# BirdHouseSchem.net
KiCad netlist of a schematic drawn in EAGLE
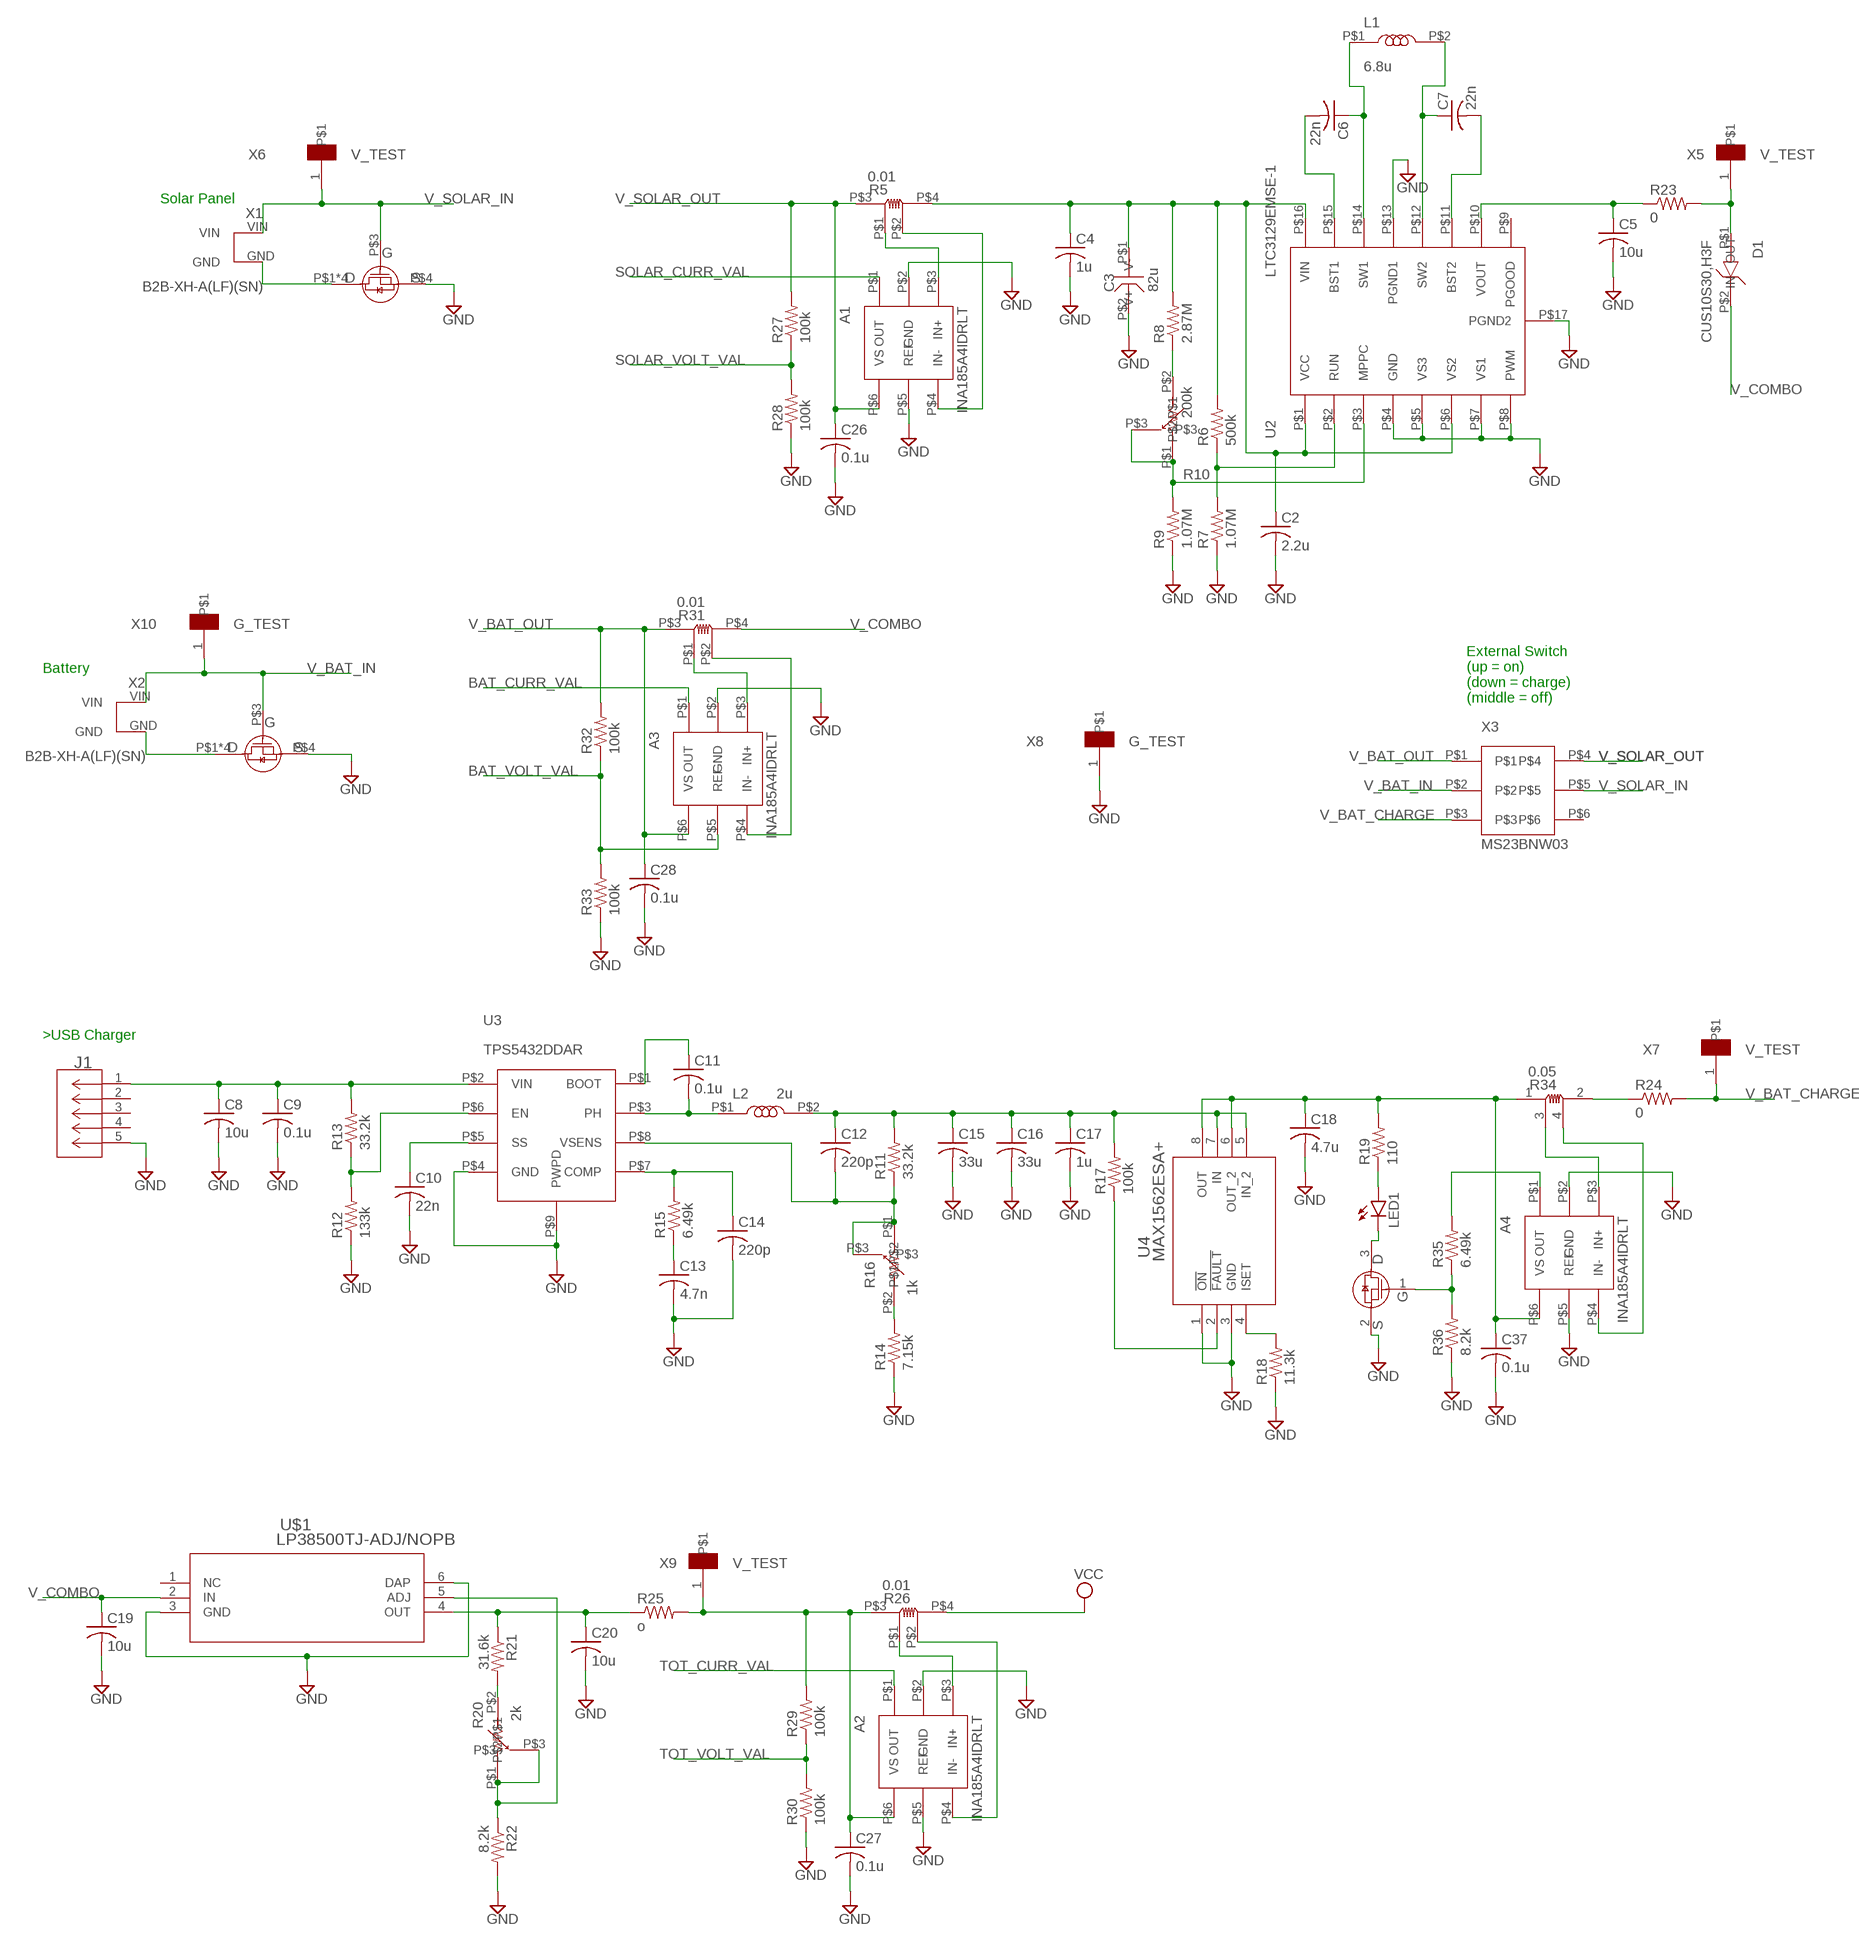
[diagram p0: schematic, sheet 1, part 1 of 2]
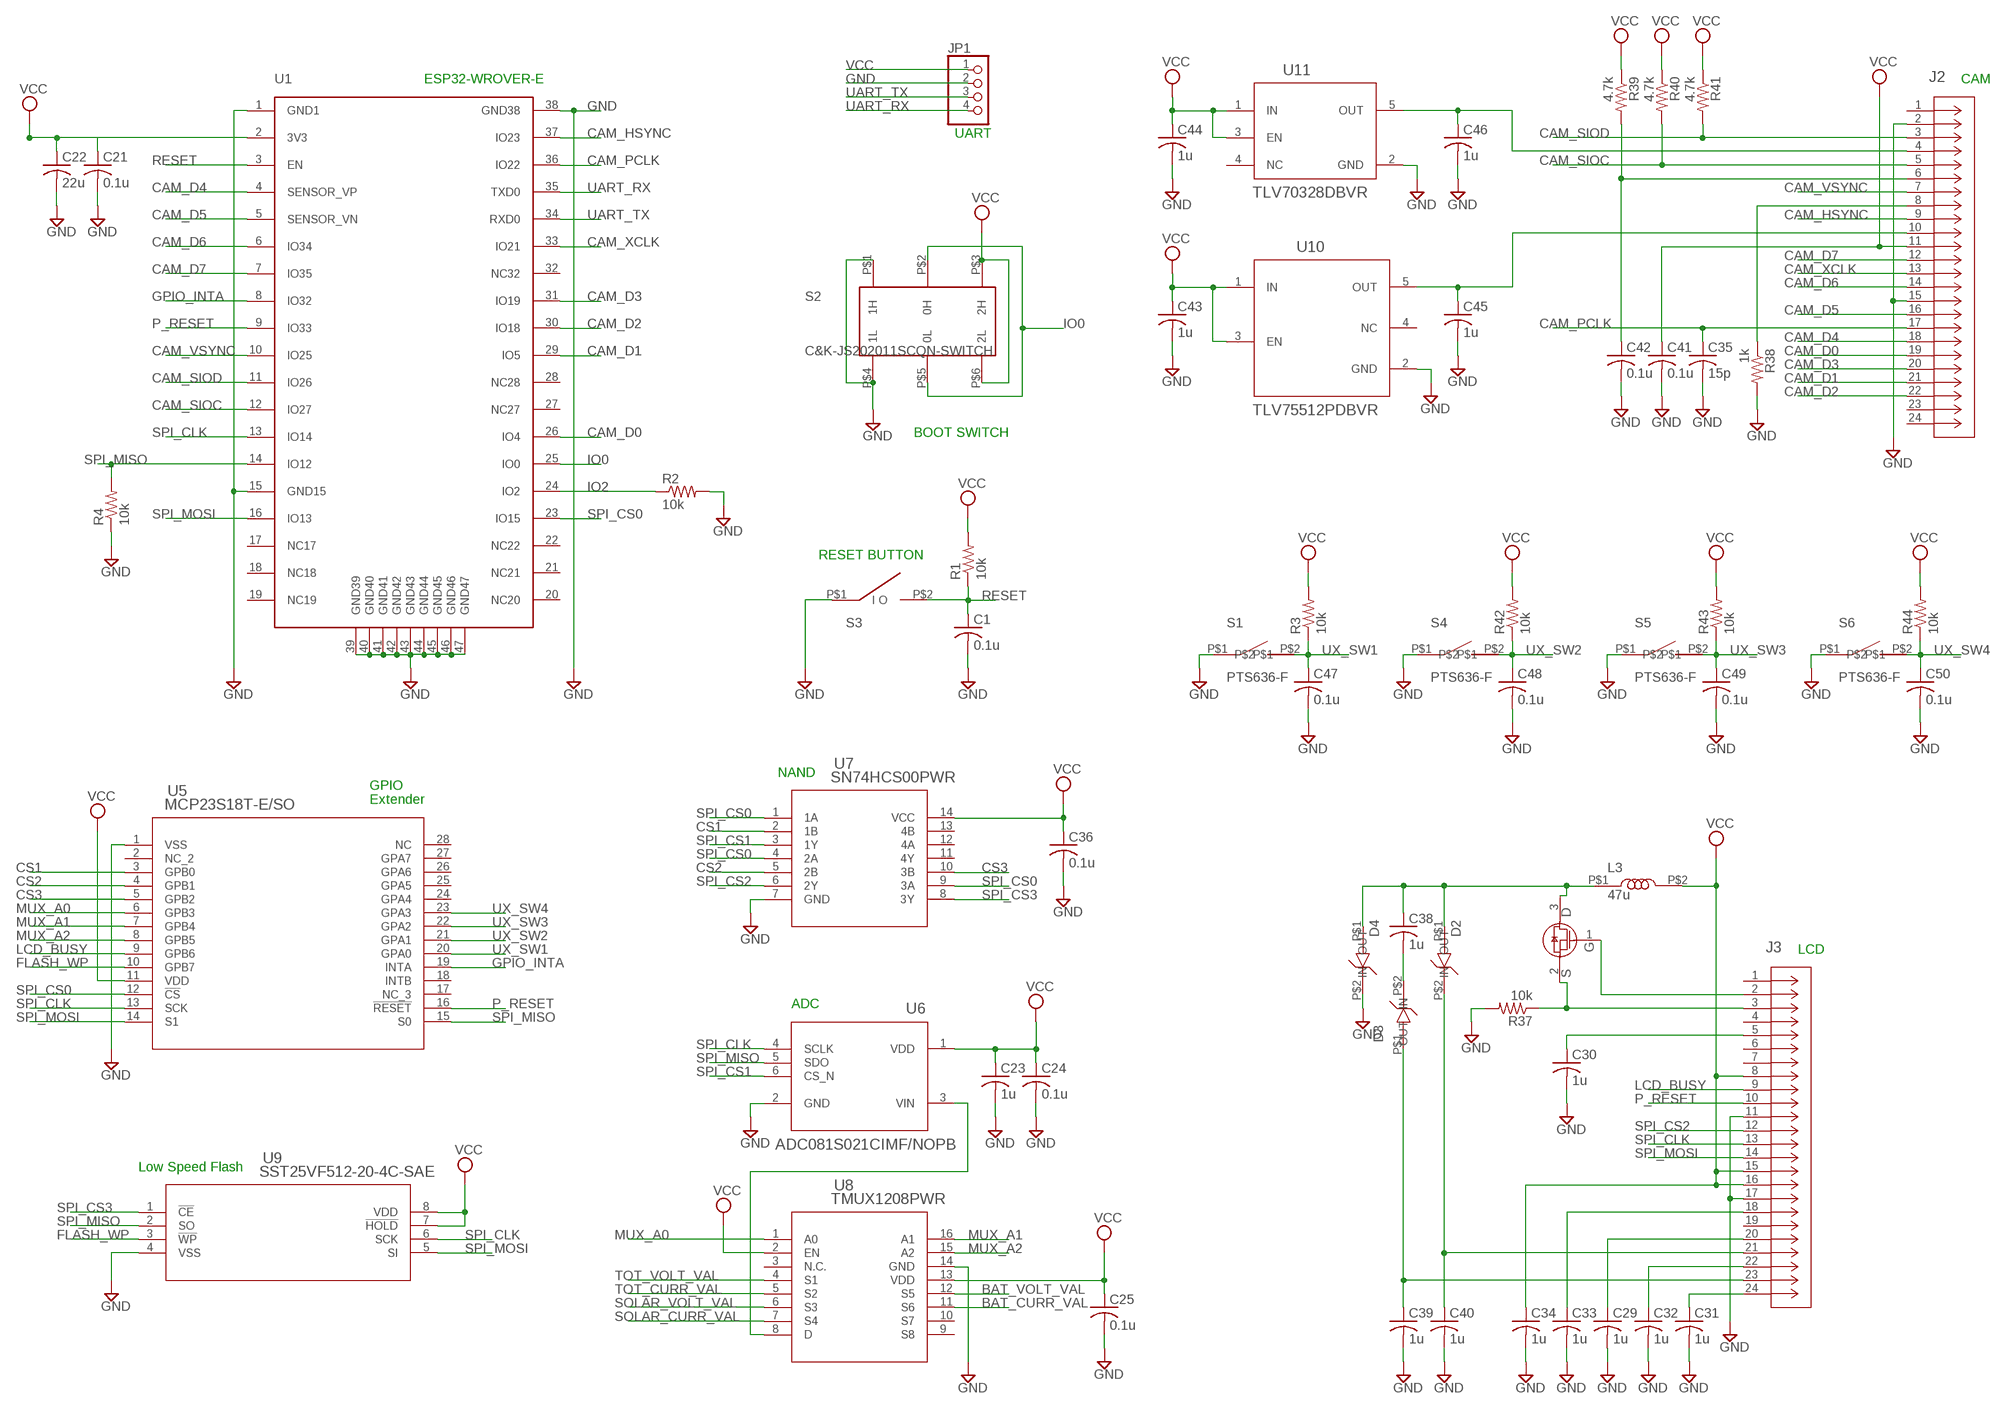
[diagram p1: schematic, sheet 1, part 2 of 2]

(export (version "E")
  (design (tool "Eeschema 10.0.6"))
  (components
    (comp (ref "A1")
      (value "INA185A4IDRLT")
      (footprint "eagle-import:SOT-6")
      (libsource (lib "eagle-import") (part "INA185A4IDRLT"))
    )
    (comp (ref "A2")
      (value "INA185A4IDRLT")
      (footprint "eagle-import:SOT-6")
      (libsource (lib "eagle-import") (part "INA185A4IDRLT"))
    )
    (comp (ref "A3")
      (value "INA185A4IDRLT")
      (footprint "eagle-import:SOT-6")
      (libsource (lib "eagle-import") (part "INA185A4IDRLT"))
    )
    (comp (ref "A4")
      (value "INA185A4IDRLT")
      (footprint "eagle-import:SOT-6")
      (libsource (lib "eagle-import") (part "INA185A4IDRLT"))
    )
    (comp (ref "C1")
      (value "0.1u")
      (footprint "eagle-import:C0805")
      (libsource (lib "eagle-import") (part "C-USC0805"))
    )
    (comp (ref "C2")
      (value "2.2u")
      (footprint "eagle-import:C0805")
      (libsource (lib "eagle-import") (part "C-USC0805"))
    )
    (comp (ref "C3")
      (value "82u")
      (footprint "eagle-import:EEE-FN1V820UP")
      (libsource (lib "eagle-import") (part "EEE-FN1V820UP"))
    )
    (comp (ref "C4")
      (value "1u")
      (footprint "eagle-import:C0805")
      (libsource (lib "eagle-import") (part "C-USC0805"))
    )
    (comp (ref "C5")
      (value "10u")
      (footprint "eagle-import:C0805")
      (libsource (lib "eagle-import") (part "C-USC0805"))
    )
    (comp (ref "C6")
      (value "22n")
      (footprint "eagle-import:C0805")
      (libsource (lib "eagle-import") (part "C-USC0805"))
    )
    (comp (ref "C7")
      (value "22n")
      (footprint "eagle-import:C0805")
      (libsource (lib "eagle-import") (part "C-USC0805"))
    )
    (comp (ref "C8")
      (value "10u")
      (footprint "eagle-import:C0805")
      (libsource (lib "eagle-import") (part "C-USC0805"))
    )
    (comp (ref "C9")
      (value "0.1u")
      (footprint "eagle-import:C0805")
      (libsource (lib "eagle-import") (part "C-USC0805"))
    )
    (comp (ref "C10")
      (value "22n")
      (footprint "eagle-import:C0805")
      (libsource (lib "eagle-import") (part "C-USC0805"))
    )
    (comp (ref "C11")
      (value "0.1u")
      (footprint "eagle-import:C0805")
      (libsource (lib "eagle-import") (part "C-USC0805"))
    )
    (comp (ref "C12")
      (value "220p")
      (footprint "eagle-import:C0805")
      (libsource (lib "eagle-import") (part "C-USC0805"))
    )
    (comp (ref "C13")
      (value "4.7n")
      (footprint "eagle-import:C0805")
      (libsource (lib "eagle-import") (part "C-USC0805"))
    )
    (comp (ref "C14")
      (value "220p")
      (footprint "eagle-import:C0805")
      (libsource (lib "eagle-import") (part "C-USC0805"))
    )
    (comp (ref "C15")
      (value "33u")
      (footprint "eagle-import:C0805")
      (libsource (lib "eagle-import") (part "C-USC0805"))
    )
    (comp (ref "C16")
      (value "33u")
      (footprint "eagle-import:C0805")
      (libsource (lib "eagle-import") (part "C-USC0805"))
    )
    (comp (ref "C17")
      (value "1u")
      (footprint "eagle-import:C0805")
      (libsource (lib "eagle-import") (part "C-USC0805"))
    )
    (comp (ref "C18")
      (value "4.7u")
      (footprint "eagle-import:C0805")
      (libsource (lib "eagle-import") (part "C-USC0805"))
    )
    (comp (ref "C19")
      (value "10u")
      (footprint "eagle-import:C0805")
      (libsource (lib "eagle-import") (part "C-USC0805"))
    )
    (comp (ref "C20")
      (value "10u")
      (footprint "eagle-import:C0805")
      (libsource (lib "eagle-import") (part "C-USC0805"))
    )
    (comp (ref "C21")
      (value "0.1u")
      (footprint "eagle-import:C0805")
      (libsource (lib "eagle-import") (part "C-USC0805"))
    )
    (comp (ref "C22")
      (value "22u")
      (footprint "eagle-import:C0805")
      (libsource (lib "eagle-import") (part "C-USC0805"))
    )
    (comp (ref "C23")
      (value "1u")
      (footprint "eagle-import:C0805")
      (libsource (lib "eagle-import") (part "C-USC0805"))
    )
    (comp (ref "C24")
      (value "0.1u")
      (footprint "eagle-import:C0805")
      (libsource (lib "eagle-import") (part "C-USC0805"))
    )
    (comp (ref "C25")
      (value "0.1u")
      (footprint "eagle-import:C0805")
      (libsource (lib "eagle-import") (part "C-USC0805"))
    )
    (comp (ref "C26")
      (value "0.1u")
      (footprint "eagle-import:C0805")
      (libsource (lib "eagle-import") (part "C-USC0805"))
    )
    (comp (ref "C27")
      (value "0.1u")
      (footprint "eagle-import:C0805")
      (libsource (lib "eagle-import") (part "C-USC0805"))
    )
    (comp (ref "C28")
      (value "0.1u")
      (footprint "eagle-import:C0805")
      (libsource (lib "eagle-import") (part "C-USC0805"))
    )
    (comp (ref "C29")
      (value "1u")
      (footprint "eagle-import:C0805")
      (libsource (lib "eagle-import") (part "C-USC0805"))
    )
    (comp (ref "C30")
      (value "1u")
      (footprint "eagle-import:C0805")
      (libsource (lib "eagle-import") (part "C-USC0805"))
    )
    (comp (ref "C31")
      (value "1u")
      (footprint "eagle-import:C0805")
      (libsource (lib "eagle-import") (part "C-USC0805"))
    )
    (comp (ref "C32")
      (value "1u")
      (footprint "eagle-import:C0805")
      (libsource (lib "eagle-import") (part "C-USC0805"))
    )
    (comp (ref "C33")
      (value "1u")
      (footprint "eagle-import:C0805")
      (libsource (lib "eagle-import") (part "C-USC0805"))
    )
    (comp (ref "C34")
      (value "1u")
      (footprint "eagle-import:C0805")
      (libsource (lib "eagle-import") (part "C-USC0805"))
    )
    (comp (ref "C35")
      (value "15p")
      (footprint "eagle-import:C0603")
      (libsource (lib "eagle-import") (part "C-USC0603"))
    )
    (comp (ref "C36")
      (value "0.1u")
      (footprint "eagle-import:C0805")
      (libsource (lib "eagle-import") (part "C-USC0805"))
    )
    (comp (ref "C37")
      (value "0.1u")
      (footprint "eagle-import:C0805")
      (libsource (lib "eagle-import") (part "C-USC0805"))
    )
    (comp (ref "C38")
      (value "1u")
      (footprint "eagle-import:C0805")
      (libsource (lib "eagle-import") (part "C-USC0805"))
    )
    (comp (ref "C39")
      (value "1u")
      (footprint "eagle-import:C0805")
      (libsource (lib "eagle-import") (part "C-USC0805"))
    )
    (comp (ref "C40")
      (value "1u")
      (footprint "eagle-import:C0805")
      (libsource (lib "eagle-import") (part "C-USC0805"))
    )
    (comp (ref "C41")
      (value "0.1u")
      (footprint "eagle-import:C0805")
      (libsource (lib "eagle-import") (part "C-USC0805"))
    )
    (comp (ref "C42")
      (value "0.1u")
      (footprint "eagle-import:C0805")
      (libsource (lib "eagle-import") (part "C-USC0805"))
    )
    (comp (ref "C43")
      (value "1u")
      (footprint "eagle-import:C0805")
      (libsource (lib "eagle-import") (part "C-USC0805"))
    )
    (comp (ref "C44")
      (value "1u")
      (footprint "eagle-import:C0805")
      (libsource (lib "eagle-import") (part "C-USC0805"))
    )
    (comp (ref "C45")
      (value "1u")
      (footprint "eagle-import:C0805")
      (libsource (lib "eagle-import") (part "C-USC0805"))
    )
    (comp (ref "C46")
      (value "1u")
      (footprint "eagle-import:C0805")
      (libsource (lib "eagle-import") (part "C-USC0805"))
    )
    (comp (ref "C47")
      (value "0.1u")
      (footprint "eagle-import:C0805")
      (libsource (lib "eagle-import") (part "C-USC0805"))
    )
    (comp (ref "C48")
      (value "0.1u")
      (footprint "eagle-import:C0805")
      (libsource (lib "eagle-import") (part "C-USC0805"))
    )
    (comp (ref "C49")
      (value "0.1u")
      (footprint "eagle-import:C0805")
      (libsource (lib "eagle-import") (part "C-USC0805"))
    )
    (comp (ref "C50")
      (value "0.1u")
      (footprint "eagle-import:C0805")
      (libsource (lib "eagle-import") (part "C-USC0805"))
    )
    (comp (ref "D1")
      (value "CUS10S30,H3F")
      (footprint "eagle-import:CUS10S30,H3F")
      (libsource (lib "eagle-import") (part "CUS10S30,H3F"))
    )
    (comp (ref "D2")
      (value "CUS10S30,H3F")
      (footprint "eagle-import:CUS10S30,H3F")
      (libsource (lib "eagle-import") (part "CUS10S30,H3F"))
    )
    (comp (ref "D3")
      (value "CUS10S30,H3F")
      (footprint "eagle-import:CUS10S30,H3F")
      (libsource (lib "eagle-import") (part "CUS10S30,H3F"))
    )
    (comp (ref "D4")
      (value "CUS10S30,H3F")
      (footprint "eagle-import:CUS10S30,H3F")
      (libsource (lib "eagle-import") (part "CUS10S30,H3F"))
    )
    (comp (ref "J1")
      (value "10103594-0001LF")
      (footprint "eagle-import:CONN_10103594-0001LF_AMP")
      (fields (field (name "COPYRIGHT") "Copyright (C) 2023 Ultra Librarian. All rights reserved."))
      (libsource (lib "eagle-import") (part "10103594-0001LF"))
    )
    (comp (ref "J2")
      (value "FH40-24S-0.5SV")
      (footprint "eagle-import:CONN_FH40-24S-0.5SV_HIR")
      (fields (field (name "COPYRIGHT") "Copyright (C) 2023 Ultra Librarian. All rights reserved."))
      (libsource (lib "eagle-import") (part "FH40-24S-0.5SV"))
    )
    (comp (ref "J3")
      (value "FH40-24S-0.5SV")
      (footprint "eagle-import:CONN_FH40-24S-0.5SV_HIR")
      (fields (field (name "COPYRIGHT") "Copyright (C) 2023 Ultra Librarian. All rights reserved."))
      (libsource (lib "eagle-import") (part "FH40-24S-0.5SV"))
    )
    (comp (ref "JP1")
      (value "PINHD-1X4")
      (footprint "eagle-import:1X04")
      (libsource (lib "eagle-import") (part "PINHD-1X4"))
    )
    (comp (ref "L1")
      (value "6.8u")
      (footprint "eagle-import:NRS8030T6R8MJGJ")
      (libsource (lib "eagle-import") (part "NRS8030T6R8MJGJ"))
    )
    (comp (ref "L2")
      (value "2u")
      (footprint "eagle-import:IHLP4040DZER2R0M11")
      (libsource (lib "eagle-import") (part "IHLP4040DZER2R0M11"))
    )
    (comp (ref "L3")
      (value "47u")
      (footprint "eagle-import:NRS8030T6R8MJGJ")
      (libsource (lib "eagle-import") (part "NRS8030T6R8MJGJ"))
    )
    (comp (ref "LED1")
      (value "LEDCHIP-LED0805")
      (footprint "eagle-import:CHIP-LED0805")
      (libsource (lib "eagle-import") (part "LEDCHIP-LED0805"))
    )
    (comp (ref "R1")
      (value "10k")
      (footprint "eagle-import:R0805")
      (libsource (lib "eagle-import") (part "R-US_R0805"))
    )
    (comp (ref "R2")
      (value "10k")
      (footprint "eagle-import:R0805")
      (libsource (lib "eagle-import") (part "R-US_R0805"))
    )
    (comp (ref "R3")
      (value "10k")
      (footprint "eagle-import:R0805")
      (libsource (lib "eagle-import") (part "R-US_R0805"))
    )
    (comp (ref "R4")
      (value "10k")
      (footprint "eagle-import:R0805")
      (libsource (lib "eagle-import") (part "R-US_R0805"))
    )
    (comp (ref "R5")
      (value "0.01")
      (footprint "eagle-import:RL1632T4F-R005-FNH")
      (libsource (lib "eagle-import") (part "RL1632T4F-R005-FNH"))
    )
    (comp (ref "R6")
      (value "500k")
      (footprint "eagle-import:R0805")
      (libsource (lib "eagle-import") (part "R-US_R0805"))
    )
    (comp (ref "R7")
      (value "1.07M")
      (footprint "eagle-import:R0805")
      (libsource (lib "eagle-import") (part "R-US_R0805"))
    )
    (comp (ref "R8")
      (value "2.87M")
      (footprint "eagle-import:R0805")
      (libsource (lib "eagle-import") (part "R-US_R0805"))
    )
    (comp (ref "R9")
      (value "1.07M")
      (footprint "eagle-import:R0805")
      (libsource (lib "eagle-import") (part "R-US_R0805"))
    )
    (comp (ref "R10")
      (value "200k")
      (footprint "eagle-import:BOURNS-3361")
      (libsource (lib "eagle-import") (part "3361P-1-202GLF"))
    )
    (comp (ref "R11")
      (value "33.2k")
      (footprint "eagle-import:R0603")
      (libsource (lib "eagle-import") (part "R-US_R0603"))
    )
    (comp (ref "R12")
      (value "133k")
      (footprint "eagle-import:R0805")
      (libsource (lib "eagle-import") (part "R-US_R0805"))
    )
    (comp (ref "R13")
      (value "33.2k")
      (footprint "eagle-import:R0603")
      (libsource (lib "eagle-import") (part "R-US_R0603"))
    )
    (comp (ref "R14")
      (value "7.15k")
      (footprint "eagle-import:R0805")
      (libsource (lib "eagle-import") (part "R-US_R0805"))
    )
    (comp (ref "R15")
      (value "6.49k")
      (footprint "eagle-import:R0805")
      (libsource (lib "eagle-import") (part "R-US_R0805"))
    )
    (comp (ref "R16")
      (value "1k")
      (footprint "eagle-import:BOURNS-3361")
      (libsource (lib "eagle-import") (part "3361P-1-202GLF"))
    )
    (comp (ref "R17")
      (value "100k")
      (footprint "eagle-import:R0805")
      (libsource (lib "eagle-import") (part "R-US_R0805"))
    )
    (comp (ref "R18")
      (value "11.3k")
      (footprint "eagle-import:R0805")
      (libsource (lib "eagle-import") (part "R-US_R0805"))
    )
    (comp (ref "R19")
      (value "110")
      (footprint "eagle-import:R0805")
      (libsource (lib "eagle-import") (part "R-US_R0805"))
    )
    (comp (ref "R20")
      (value "2k")
      (footprint "eagle-import:BOURNS-3361")
      (libsource (lib "eagle-import") (part "3361P-1-202GLF"))
    )
    (comp (ref "R21")
      (value "31.6k")
      (footprint "eagle-import:R0805")
      (libsource (lib "eagle-import") (part "R-US_R0805"))
    )
    (comp (ref "R22")
      (value "8.2k")
      (footprint "eagle-import:R0805")
      (libsource (lib "eagle-import") (part "R-US_R0805"))
    )
    (comp (ref "R23")
      (value "0")
      (footprint "eagle-import:R0805")
      (libsource (lib "eagle-import") (part "R-US_R0805"))
    )
    (comp (ref "R24")
      (value "0")
      (footprint "eagle-import:R0805")
      (libsource (lib "eagle-import") (part "R-US_R0805"))
    )
    (comp (ref "R25")
      (value "o")
      (footprint "eagle-import:R0805")
      (libsource (lib "eagle-import") (part "R-US_R0805"))
    )
    (comp (ref "R26")
      (value "0.01")
      (footprint "eagle-import:RL1632T4F-R005-FNH")
      (libsource (lib "eagle-import") (part "RL1632T4F-R005-FNH"))
    )
    (comp (ref "R27")
      (value "100k")
      (footprint "eagle-import:R0805")
      (libsource (lib "eagle-import") (part "R-US_R0805"))
    )
    (comp (ref "R28")
      (value "100k")
      (footprint "eagle-import:R0805")
      (libsource (lib "eagle-import") (part "R-US_R0805"))
    )
    (comp (ref "R29")
      (value "100k")
      (footprint "eagle-import:R0805")
      (libsource (lib "eagle-import") (part "R-US_R0805"))
    )
    (comp (ref "R30")
      (value "100k")
      (footprint "eagle-import:R0805")
      (libsource (lib "eagle-import") (part "R-US_R0805"))
    )
    (comp (ref "R31")
      (value "0.01")
      (footprint "eagle-import:RL1632T4F-R005-FNH")
      (libsource (lib "eagle-import") (part "RL1632T4F-R005-FNH"))
    )
    (comp (ref "R32")
      (value "100k")
      (footprint "eagle-import:R0805")
      (libsource (lib "eagle-import") (part "R-US_R0805"))
    )
    (comp (ref "R33")
      (value "100k")
      (footprint "eagle-import:R0805")
      (libsource (lib "eagle-import") (part "R-US_R0805"))
    )
    (comp (ref "R34")
      (value "0.05")
      (footprint "eagle-import:RL0816T4F-4")
      (libsource (lib "eagle-import") (part "RL0816T4F-4"))
    )
    (comp (ref "R35")
      (value "6.49k")
      (footprint "eagle-import:R0805")
      (libsource (lib "eagle-import") (part "R-US_R0805"))
    )
    (comp (ref "R36")
      (value "8.2k")
      (footprint "eagle-import:R0805")
      (libsource (lib "eagle-import") (part "R-US_R0805"))
    )
    (comp (ref "R37")
      (value "10k")
      (footprint "eagle-import:R0805")
      (libsource (lib "eagle-import") (part "R-US_R0805"))
    )
    (comp (ref "R38")
      (value "1k")
      (footprint "eagle-import:R0805")
      (libsource (lib "eagle-import") (part "R-US_R0805"))
    )
    (comp (ref "R39")
      (value "4.7k")
      (footprint "eagle-import:R0805")
      (libsource (lib "eagle-import") (part "R-US_R0805"))
    )
    (comp (ref "R40")
      (value "4.7k")
      (footprint "eagle-import:R0805")
      (libsource (lib "eagle-import") (part "R-US_R0805"))
    )
    (comp (ref "R41")
      (value "4.7k")
      (footprint "eagle-import:R0805")
      (libsource (lib "eagle-import") (part "R-US_R0805"))
    )
    (comp (ref "R42")
      (value "10k")
      (footprint "eagle-import:R0805")
      (libsource (lib "eagle-import") (part "R-US_R0805"))
    )
    (comp (ref "R43")
      (value "10k")
      (footprint "eagle-import:R0805")
      (libsource (lib "eagle-import") (part "R-US_R0805"))
    )
    (comp (ref "R44")
      (value "10k")
      (footprint "eagle-import:R0805")
      (libsource (lib "eagle-import") (part "R-US_R0805"))
    )
    (comp (ref "S1")
      (value "PTS636-F")
      (footprint "eagle-import:PTS636-F")
      (libsource (lib "eagle-import") (part "PTS636-F"))
    )
    (comp (ref "S2")
      (value "C&K-JS202011SCQN-SWITCH")
      (footprint "eagle-import:C&K-JS202011SCQN-SWITCH")
      (libsource (lib "eagle-import") (part "C&K-JS202011SCQN-SWITCH"))
    )
    (comp (ref "S3")
      (value "C&K-PTS636SL43SMTRLFS-PUSHBUTTON")
      (footprint "eagle-import:C&K-PTS636SL43SMTRLFS-PUSHBUTTON")
      (libsource (lib "eagle-import") (part "C&K-PTS636SL43SMTRLFS-PUSHBUTTON"))
    )
    (comp (ref "S4")
      (value "PTS636-F")
      (footprint "eagle-import:PTS636-F")
      (libsource (lib "eagle-import") (part "PTS636-F"))
    )
    (comp (ref "S5")
      (value "PTS636-F")
      (footprint "eagle-import:PTS636-F")
      (libsource (lib "eagle-import") (part "PTS636-F"))
    )
    (comp (ref "S6")
      (value "PTS636-F")
      (footprint "eagle-import:PTS636-F")
      (libsource (lib "eagle-import") (part "PTS636-F"))
    )
    (comp (ref "TR1")
      (value "SI3464DV-T1-BE3")
      (footprint "eagle-import:TSOP-6")
      (libsource (lib "eagle-import") (part "SI3464DV-T1-BE3"))
    )
    (comp (ref "TR2")
      (value "SI3464DV-T1-BE3")
      (footprint "eagle-import:TSOP-6")
      (libsource (lib "eagle-import") (part "SI3464DV-T1-BE3"))
    )
    (comp (ref "TR3")
      (value "NX6008NBKW")
      (footprint "eagle-import:SOT323")
      (libsource (lib "eagle-import") (part "NX6008NBKW"))
    )
    (comp (ref "TR4")
      (value "PMF250XNEX")
      (footprint "eagle-import:SOT323")
      (libsource (lib "eagle-import") (part "PMF250XNEX"))
    )
    (comp (ref "U$1")
      (value "LP38500TJ-ADJ/NOPB")
      (footprint "eagle-import:TJ5A")
      (fields (field (name "COPYRIGHT") "Copyright (C) 2023 Ultra Librarian. All rights reserved."))
      (libsource (lib "eagle-import") (part "LP38500TJ-ADJ/NOPB"))
    )
    (comp (ref "U1")
      (value "ESP32-WROVER-E")
      (footprint "eagle-import:ESP32-WROVER-E")
      (libsource (lib "eagle-import") (part "ESP32-WROVER-E"))
    )
    (comp (ref "U2")
      (value "LTC3129EMSE-1")
      (footprint "eagle-import:LTC3129EMSE-1")
      (libsource (lib "eagle-import") (part "LTC3129EMSE-1"))
    )
    (comp (ref "U3")
      (value "TPS5432DDAR")
      (footprint "eagle-import:TPS5432DDAR")
      (libsource (lib "eagle-import") (part "TPS5432DDAR"))
    )
    (comp (ref "U4")
      (value "MAX1562ESA+")
      (footprint "eagle-import:21-0041_S8+2_MXM")
      (fields (field (name "COPYRIGHT") "Copyright (C) 2023 Ultra Librarian. All rights reserved."))
      (libsource (lib "eagle-import") (part "MAX1562ESA+"))
    )
    (comp (ref "U5")
      (value "MCP23S18T-E/SO")
      (footprint "eagle-import:SOIC28-W_MC_MCH")
      (fields (field (name "COPYRIGHT") "Copyright (C) 2023 Ultra Librarian. All rights reserved."))
      (libsource (lib "eagle-import") (part "MCP23S18T-E/SO"))
    )
    (comp (ref "U6")
      (value "ADC081S021CIMF/NOPB")
      (footprint "eagle-import:DBV0006A_N")
      (fields (field (name "COPYRIGHT") "Copyright (C) 2023 Ultra Librarian. All rights reserved."))
      (libsource (lib "eagle-import") (part "ADC081S021CIMF/NOPB"))
    )
    (comp (ref "U7")
      (value "SN74HCS00PWR")
      (footprint "eagle-import:TSSOP14_PW_TEX")
      (fields (field (name "COPYRIGHT") "Copyright (C) 2023 Ultra Librarian. All rights reserved."))
      (libsource (lib "eagle-import") (part "SN74HCS00PWR"))
    )
    (comp (ref "U8")
      (value "TMUX1208PWR")
      (footprint "eagle-import:PW_16_TEX")
      (fields (field (name "COPYRIGHT") "Copyright (C) 2023 Ultra Librarian. All rights reserved."))
      (libsource (lib "eagle-import") (part "TMUX1208PWR"))
    )
    (comp (ref "U9")
      (value "SST25VF512-20-4C-SAE")
      (footprint "eagle-import:SOIC8_SA_SST_MCH")
      (fields (field (name "COPYRIGHT") "Copyright (C) 2023 Ultra Librarian. All rights reserved."))
      (libsource (lib "eagle-import") (part "SST25VF512-20-4C-SAE"))
    )
    (comp (ref "U10")
      (value "TLV75512PDBVR")
      (footprint "eagle-import:DBV0005A_N")
      (fields (field (name "COPYRIGHT") "Copyright (C) 2023 Ultra Librarian. All rights reserved."))
      (libsource (lib "eagle-import") (part "TLV75512PDBVR"))
    )
    (comp (ref "U11")
      (value "TLV70328DBVR")
      (footprint "eagle-import:DBV0005A-IPC_A")
      (fields (field (name "COPYRIGHT") "Copyright (C) 2023 Ultra Librarian. All rights reserved."))
      (libsource (lib "eagle-import") (part "TLV70328DBVR"))
    )
    (comp (ref "X1")
      (value "B2B-XH-A(LF)(SN)")
      (footprint "eagle-import:B2B-XH-A(LF)(SN)")
      (libsource (lib "eagle-import") (part "B2B-XH-A(LF)(SN)"))
    )
    (comp (ref "X2")
      (value "B2B-XH-A(LF)(SN)")
      (footprint "eagle-import:B2B-XH-A(LF)(SN)")
      (libsource (lib "eagle-import") (part "B2B-XH-A(LF)(SN)"))
    )
    (comp (ref "X3")
      (value "MS23BNW03")
      (footprint "eagle-import:MS23BNW03")
      (libsource (lib "eagle-import") (part "MS23BNW03"))
    )
    (comp (ref "X5")
      (value "V_TEST")
      (footprint "eagle-import:V_TEST")
      (libsource (lib "eagle-import") (part "V_TEST"))
    )
    (comp (ref "X6")
      (value "V_TEST")
      (footprint "eagle-import:V_TEST")
      (libsource (lib "eagle-import") (part "V_TEST"))
    )
    (comp (ref "X7")
      (value "V_TEST")
      (footprint "eagle-import:V_TEST")
      (libsource (lib "eagle-import") (part "V_TEST"))
    )
    (comp (ref "X8")
      (value "G_TEST")
      (footprint "eagle-import:V_TEST")
      (libsource (lib "eagle-import") (part "V_TEST"))
    )
    (comp (ref "X9")
      (value "V_TEST")
      (footprint "eagle-import:V_TEST")
      (libsource (lib "eagle-import") (part "V_TEST"))
    )
    (comp (ref "X10")
      (value "G_TEST")
      (footprint "eagle-import:V_TEST")
      (libsource (lib "eagle-import") (part "V_TEST"))
    )
  )
  (nets
    (net (code "1") (name "/BAT_CURR_VAL") (class "Default")
      (node (ref "A3") (pin "P$1") (pinfunction "OUT_P$1") (pintype "bidirectional"))
      (node (ref "U8") (pin "11") (pinfunction "S6_11") (pintype "bidirectional"))
    )
    (net (code "2") (name "/BAT_VOLT_VAL") (class "Default")
      (node (ref "A3") (pin "P$5") (pinfunction "REF_P$5") (pintype "bidirectional"))
      (node (ref "R32") (pin "1") (pinfunction "1_1") (pintype "passive"))
      (node (ref "R33") (pin "2") (pinfunction "2_2") (pintype "passive"))
      (node (ref "U8") (pin "12") (pinfunction "S5_12") (pintype "bidirectional"))
    )
    (net (code "3") (name "/CAM_D0") (class "Default")
      (node (ref "J2") (pin "19") (pinfunction "19_19") (pintype "passive"))
      (node (ref "U1") (pin "26") (pinfunction "IO4_26") (pintype "bidirectional"))
    )
    (net (code "4") (name "/CAM_D1") (class "Default")
      (node (ref "J2") (pin "21") (pinfunction "21_21") (pintype "passive"))
      (node (ref "U1") (pin "29") (pinfunction "IO5_29") (pintype "bidirectional"))
    )
    (net (code "5") (name "/CAM_D2") (class "Default")
      (node (ref "J2") (pin "22") (pinfunction "22_22") (pintype "passive"))
      (node (ref "U1") (pin "30") (pinfunction "IO18_30") (pintype "bidirectional"))
    )
    (net (code "6") (name "/CAM_D3") (class "Default")
      (node (ref "J2") (pin "20") (pinfunction "20_20") (pintype "passive"))
      (node (ref "U1") (pin "31") (pinfunction "IO19_31") (pintype "bidirectional"))
    )
    (net (code "7") (name "/CAM_D4") (class "Default")
      (node (ref "J2") (pin "18") (pinfunction "18_18") (pintype "passive"))
      (node (ref "U1") (pin "4") (pinfunction "SENSOR_VP_4") (pintype "input"))
    )
    (net (code "8") (name "/CAM_D5") (class "Default")
      (node (ref "J2") (pin "16") (pinfunction "16_16") (pintype "passive"))
      (node (ref "U1") (pin "5") (pinfunction "SENSOR_VN_5") (pintype "input"))
    )
    (net (code "9") (name "/CAM_D6") (class "Default")
      (node (ref "J2") (pin "14") (pinfunction "14_14") (pintype "passive"))
      (node (ref "U1") (pin "6") (pinfunction "IO34_6") (pintype "input"))
    )
    (net (code "10") (name "/CAM_D7") (class "Default")
      (node (ref "J2") (pin "12") (pinfunction "12_12") (pintype "passive"))
      (node (ref "U1") (pin "7") (pinfunction "IO35_7") (pintype "input"))
    )
    (net (code "11") (name "/CAM_HSYNC") (class "Default")
      (node (ref "J2") (pin "9") (pinfunction "9_9") (pintype "passive"))
      (node (ref "U1") (pin "37") (pinfunction "IO23_37") (pintype "bidirectional"))
    )
    (net (code "12") (name "/CAM_PCLK") (class "Default")
      (node (ref "C35") (pin "1") (pinfunction "1_1") (pintype "passive"))
      (node (ref "J2") (pin "17") (pinfunction "17_17") (pintype "passive"))
      (node (ref "U1") (pin "36") (pinfunction "IO22_36") (pintype "bidirectional"))
    )
    (net (code "13") (name "/CAM_SIOC") (class "Default")
      (node (ref "J2") (pin "5") (pinfunction "5_5") (pintype "passive"))
      (node (ref "R40") (pin "2") (pinfunction "2_2") (pintype "passive"))
      (node (ref "U1") (pin "12") (pinfunction "IO27_12") (pintype "bidirectional"))
    )
    (net (code "14") (name "/CAM_SIOD") (class "Default")
      (node (ref "J2") (pin "3") (pinfunction "3_3") (pintype "passive"))
      (node (ref "R41") (pin "2") (pinfunction "2_2") (pintype "passive"))
      (node (ref "U1") (pin "11") (pinfunction "IO26_11") (pintype "bidirectional"))
    )
    (net (code "15") (name "/CAM_VSYNC") (class "Default")
      (node (ref "J2") (pin "7") (pinfunction "7_7") (pintype "passive"))
      (node (ref "U1") (pin "10") (pinfunction "IO25_10") (pintype "bidirectional"))
    )
    (net (code "16") (name "/CAM_XCLK") (class "Default")
      (node (ref "J2") (pin "13") (pinfunction "13_13") (pintype "passive"))
      (node (ref "U1") (pin "33") (pinfunction "IO21_33") (pintype "bidirectional"))
    )
    (net (code "17") (name "/CS1") (class "Default")
      (node (ref "U5") (pin "3") (pinfunction "GPB0_3") (pintype "passive"))
      (node (ref "U7") (pin "2") (pinfunction "1B_2") (pintype "bidirectional"))
    )
    (net (code "18") (name "/CS2") (class "Default")
      (node (ref "U5") (pin "4") (pinfunction "GPB1_4") (pintype "passive"))
      (node (ref "U7") (pin "5") (pinfunction "2B_5") (pintype "bidirectional"))
    )
    (net (code "19") (name "/CS3") (class "Default")
      (node (ref "U5") (pin "5") (pinfunction "GPB2_5") (pintype "passive"))
      (node (ref "U7") (pin "10") (pinfunction "3B_10") (pintype "bidirectional"))
    )
    (net (code "20") (name "/FLASH_WP") (class "Default")
      (node (ref "U5") (pin "10") (pinfunction "GPB7_10") (pintype "passive"))
      (node (ref "U9") (pin "3") (pinfunction "~{WP}_3") (pintype "input"))
    )
    (net (code "21") (name "/GPIO_INTA") (class "Default")
      (node (ref "U1") (pin "8") (pinfunction "IO32_8") (pintype "bidirectional"))
      (node (ref "U5") (pin "19") (pinfunction "INTA_19") (pintype "passive"))
    )
    (net (code "22") (name "/IO0") (class "Default")
      (node (ref "S2") (pin "P$2") (pinfunction "0H_P$2") (pintype "bidirectional"))
      (node (ref "S2") (pin "P$5") (pinfunction "0L_P$5") (pintype "bidirectional"))
      (node (ref "U1") (pin "25") (pinfunction "IO0_25") (pintype "bidirectional"))
    )
    (net (code "23") (name "/IO2") (class "Default")
      (node (ref "R2") (pin "1") (pinfunction "1_1") (pintype "passive"))
      (node (ref "U1") (pin "24") (pinfunction "IO2_24") (pintype "bidirectional"))
    )
    (net (code "24") (name "/LCD_BUSY") (class "Default")
      (node (ref "J3") (pin "9") (pinfunction "9_9") (pintype "passive"))
      (node (ref "U5") (pin "9") (pinfunction "GPB6_9") (pintype "passive"))
    )
    (net (code "25") (name "/MUX_A0") (class "Default")
      (node (ref "U5") (pin "6") (pinfunction "GPB3_6") (pintype "passive"))
      (node (ref "U8") (pin "1") (pinfunction "A0_1") (pintype "bidirectional"))
    )
    (net (code "26") (name "/MUX_A1") (class "Default")
      (node (ref "U5") (pin "7") (pinfunction "GPB4_7") (pintype "passive"))
      (node (ref "U8") (pin "16") (pinfunction "A1_16") (pintype "bidirectional"))
    )
    (net (code "27") (name "/MUX_A2") (class "Default")
      (node (ref "U5") (pin "8") (pinfunction "GPB5_8") (pintype "passive"))
      (node (ref "U8") (pin "15") (pinfunction "A2_15") (pintype "bidirectional"))
    )
    (net (code "28") (name "/P_RESET") (class "Default")
      (node (ref "J3") (pin "10") (pinfunction "10_10") (pintype "passive"))
      (node (ref "U1") (pin "9") (pinfunction "IO33_9") (pintype "bidirectional"))
      (node (ref "U5") (pin "16") (pinfunction "~{RESET}_16") (pintype "passive"))
    )
    (net (code "29") (name "/RESET") (class "Default")
      (node (ref "C1") (pin "1") (pinfunction "1_1") (pintype "passive"))
      (node (ref "R1") (pin "1") (pinfunction "1_1") (pintype "passive"))
      (node (ref "S3") (pin "P$2") (pinfunction "O_P$2") (pintype "bidirectional"))
      (node (ref "U1") (pin "3") (pinfunction "EN_3") (pintype "input"))
    )
    (net (code "30") (name "/SOLAR_CURR_VAL") (class "Default")
      (node (ref "A1") (pin "P$1") (pinfunction "OUT_P$1") (pintype "bidirectional"))
      (node (ref "U8") (pin "7") (pinfunction "S4_7") (pintype "bidirectional"))
    )
    (net (code "31") (name "/SOLAR_VOLT_VAL") (class "Default")
      (node (ref "R27") (pin "1") (pinfunction "1_1") (pintype "passive"))
      (node (ref "R28") (pin "2") (pinfunction "2_2") (pintype "passive"))
      (node (ref "U8") (pin "6") (pinfunction "S3_6") (pintype "bidirectional"))
    )
    (net (code "32") (name "/SPI_CLK") (class "Default")
      (node (ref "J3") (pin "13") (pinfunction "13_13") (pintype "passive"))
      (node (ref "U1") (pin "13") (pinfunction "IO14_13") (pintype "bidirectional"))
      (node (ref "U5") (pin "13") (pinfunction "SCK_13") (pintype "passive"))
      (node (ref "U6") (pin "4") (pinfunction "SCLK_4") (pintype "input"))
      (node (ref "U9") (pin "6") (pinfunction "SCK_6") (pintype "input"))
    )
    (net (code "33") (name "/SPI_CS0") (class "Default")
      (node (ref "U1") (pin "23") (pinfunction "IO15_23") (pintype "bidirectional"))
      (node (ref "U5") (pin "12") (pinfunction "~{CS}_12") (pintype "passive"))
      (node (ref "U7") (pin "1") (pinfunction "1A_1") (pintype "bidirectional"))
      (node (ref "U7") (pin "4") (pinfunction "2A_4") (pintype "bidirectional"))
      (node (ref "U7") (pin "9") (pinfunction "3A_9") (pintype "bidirectional"))
    )
    (net (code "34") (name "/SPI_CS1") (class "Default")
      (node (ref "U6") (pin "6") (pinfunction "CS_N_6") (pintype "input"))
      (node (ref "U7") (pin "3") (pinfunction "1Y_3") (pintype "bidirectional"))
    )
    (net (code "35") (name "/SPI_CS2") (class "Default")
      (node (ref "J3") (pin "12") (pinfunction "12_12") (pintype "passive"))
      (node (ref "U7") (pin "6") (pinfunction "2Y_6") (pintype "bidirectional"))
    )
    (net (code "36") (name "/SPI_CS3") (class "Default")
      (node (ref "U7") (pin "8") (pinfunction "3Y_8") (pintype "bidirectional"))
      (node (ref "U9") (pin "1") (pinfunction "~{CE}_1") (pintype "input"))
    )
    (net (code "37") (name "/SPI_MISO") (class "Default")
      (node (ref "R4") (pin "2") (pinfunction "2_2") (pintype "passive"))
      (node (ref "U1") (pin "14") (pinfunction "IO12_14") (pintype "bidirectional"))
      (node (ref "U5") (pin "15") (pinfunction "S0_15") (pintype "passive"))
      (node (ref "U6") (pin "5") (pinfunction "SDO_5") (pintype "output"))
      (node (ref "U9") (pin "2") (pinfunction "SO_2") (pintype "output"))
    )
    (net (code "38") (name "/SPI_MOSI") (class "Default")
      (node (ref "J3") (pin "14") (pinfunction "14_14") (pintype "passive"))
      (node (ref "U1") (pin "16") (pinfunction "IO13_16") (pintype "bidirectional"))
      (node (ref "U5") (pin "14") (pinfunction "S1_14") (pintype "passive"))
      (node (ref "U9") (pin "5") (pinfunction "SI_5") (pintype "input"))
    )
    (net (code "39") (name "/TOT_CURR_VAL") (class "Default")
      (node (ref "A2") (pin "P$1") (pinfunction "OUT_P$1") (pintype "bidirectional"))
      (node (ref "U8") (pin "5") (pinfunction "S2_5") (pintype "bidirectional"))
    )
    (net (code "40") (name "/TOT_VOLT_VAL") (class "Default")
      (node (ref "R29") (pin "1") (pinfunction "1_1") (pintype "passive"))
      (node (ref "R30") (pin "2") (pinfunction "2_2") (pintype "passive"))
      (node (ref "U8") (pin "4") (pinfunction "S1_4") (pintype "bidirectional"))
    )
    (net (code "41") (name "/UART_RX") (class "Default")
      (node (ref "JP1") (pin "4") (pinfunction "4_4") (pintype "passive"))
      (node (ref "U1") (pin "35") (pinfunction "TXD0_35") (pintype "bidirectional"))
    )
    (net (code "42") (name "/UART_TX") (class "Default")
      (node (ref "JP1") (pin "3") (pinfunction "3_3") (pintype "passive"))
      (node (ref "U1") (pin "34") (pinfunction "RXD0_34") (pintype "bidirectional"))
    )
    (net (code "43") (name "/UX_SW1") (class "Default")
      (node (ref "C47") (pin "1") (pinfunction "1_1") (pintype "passive"))
      (node (ref "R3") (pin "1") (pinfunction "1_1") (pintype "passive"))
      (node (ref "S1") (pin "P$2") (pinfunction "P$2_P$2") (pintype "bidirectional"))
      (node (ref "U5") (pin "20") (pinfunction "GPA0_20") (pintype "passive"))
    )
    (net (code "44") (name "/UX_SW2") (class "Default")
      (node (ref "C48") (pin "1") (pinfunction "1_1") (pintype "passive"))
      (node (ref "R42") (pin "1") (pinfunction "1_1") (pintype "passive"))
      (node (ref "S4") (pin "P$2") (pinfunction "P$2_P$2") (pintype "bidirectional"))
      (node (ref "U5") (pin "21") (pinfunction "GPA1_21") (pintype "passive"))
    )
    (net (code "45") (name "/UX_SW3") (class "Default")
      (node (ref "C49") (pin "1") (pinfunction "1_1") (pintype "passive"))
      (node (ref "R43") (pin "1") (pinfunction "1_1") (pintype "passive"))
      (node (ref "S5") (pin "P$2") (pinfunction "P$2_P$2") (pintype "bidirectional"))
      (node (ref "U5") (pin "22") (pinfunction "GPA2_22") (pintype "passive"))
    )
    (net (code "46") (name "/UX_SW4") (class "Default")
      (node (ref "C50") (pin "1") (pinfunction "1_1") (pintype "passive"))
      (node (ref "R44") (pin "1") (pinfunction "1_1") (pintype "passive"))
      (node (ref "S6") (pin "P$2") (pinfunction "P$2_P$2") (pintype "bidirectional"))
      (node (ref "U5") (pin "23") (pinfunction "GPA3_23") (pintype "passive"))
    )
    (net (code "47") (name "/V_BAT_CHARGE") (class "Default")
      (node (ref "R24") (pin "2") (pinfunction "2_2") (pintype "passive"))
      (node (ref "X3") (pin "P$3") (pinfunction "P$3_P$3") (pintype "bidirectional"))
      (node (ref "X7") (pin "1") (pinfunction "P$1_1") (pintype "bidirectional"))
    )
    (net (code "48") (name "/V_BAT_IN") (class "Default")
      (node (ref "TR2") (pin "P$3") (pinfunction "G_P$3") (pintype "bidirectional"))
      (node (ref "X10") (pin "1") (pinfunction "P$1_1") (pintype "bidirectional"))
      (node (ref "X2") (pin "VIN") (pinfunction "VIN_VIN") (pintype "bidirectional"))
      (node (ref "X3") (pin "P$2") (pinfunction "P$2_P$2") (pintype "bidirectional"))
    )
    (net (code "49") (name "/V_BAT_OUT") (class "Default")
      (node (ref "A3") (pin "P$6") (pinfunction "VS_P$6") (pintype "bidirectional"))
      (node (ref "C28") (pin "1") (pinfunction "1_1") (pintype "passive"))
      (node (ref "R31") (pin "P$3") (pinfunction "I1_P$3") (pintype "bidirectional"))
      (node (ref "R32") (pin "2") (pinfunction "2_2") (pintype "passive"))
      (node (ref "X3") (pin "P$1") (pinfunction "P$1_P$1") (pintype "bidirectional"))
    )
    (net (code "50") (name "/V_COMBO") (class "Default")
      (node (ref "C19") (pin "1") (pinfunction "1_1") (pintype "passive"))
      (node (ref "D1") (pin "P$2") (pinfunction "OUT_P$2") (pintype "bidirectional"))
      (node (ref "R31") (pin "P$4") (pinfunction "I2_P$4") (pintype "bidirectional"))
      (node (ref "U$1") (pin "2") (pinfunction "IN_2") (pintype "power_in"))
    )
    (net (code "51") (name "/V_SOLAR_IN") (class "Default")
      (node (ref "TR1") (pin "P$3") (pinfunction "G_P$3") (pintype "bidirectional"))
      (node (ref "X1") (pin "VIN") (pinfunction "VIN_VIN") (pintype "bidirectional"))
      (node (ref "X3") (pin "P$5") (pinfunction "P$5_P$5") (pintype "bidirectional"))
      (node (ref "X6") (pin "1") (pinfunction "P$1_1") (pintype "bidirectional"))
    )
    (net (code "52") (name "/V_SOLAR_OUT") (class "Default")
      (node (ref "A1") (pin "P$6") (pinfunction "VS_P$6") (pintype "bidirectional"))
      (node (ref "C26") (pin "1") (pinfunction "1_1") (pintype "passive"))
      (node (ref "R27") (pin "2") (pinfunction "2_2") (pintype "passive"))
      (node (ref "R5") (pin "P$3") (pinfunction "I1_P$3") (pintype "bidirectional"))
      (node (ref "X3") (pin "P$4") (pinfunction "P$4_P$4") (pintype "bidirectional"))
    )
    (net (code "53") (name "GND") (class "Default")
      (node (ref "A1") (pin "P$2") (pinfunction "GND_P$2") (pintype "bidirectional"))
      (node (ref "A1") (pin "P$5") (pinfunction "REF_P$5") (pintype "bidirectional"))
      (node (ref "A2") (pin "P$2") (pinfunction "GND_P$2") (pintype "bidirectional"))
      (node (ref "A2") (pin "P$5") (pinfunction "REF_P$5") (pintype "bidirectional"))
      (node (ref "A3") (pin "P$2") (pinfunction "GND_P$2") (pintype "bidirectional"))
      (node (ref "A4") (pin "P$2") (pinfunction "GND_P$2") (pintype "bidirectional"))
      (node (ref "A4") (pin "P$5") (pinfunction "REF_P$5") (pintype "bidirectional"))
      (node (ref "C1") (pin "2") (pinfunction "2_2") (pintype "passive"))
      (node (ref "C10") (pin "2") (pinfunction "2_2") (pintype "passive"))
      (node (ref "C13") (pin "2") (pinfunction "2_2") (pintype "passive"))
      (node (ref "C14") (pin "2") (pinfunction "2_2") (pintype "passive"))
      (node (ref "C15") (pin "2") (pinfunction "2_2") (pintype "passive"))
      (node (ref "C16") (pin "2") (pinfunction "2_2") (pintype "passive"))
      (node (ref "C17") (pin "2") (pinfunction "2_2") (pintype "passive"))
      (node (ref "C18") (pin "2") (pinfunction "2_2") (pintype "passive"))
      (node (ref "C19") (pin "2") (pinfunction "2_2") (pintype "passive"))
      (node (ref "C2") (pin "2") (pinfunction "2_2") (pintype "passive"))
      (node (ref "C20") (pin "2") (pinfunction "2_2") (pintype "passive"))
      (node (ref "C21") (pin "2") (pinfunction "2_2") (pintype "passive"))
      (node (ref "C22") (pin "2") (pinfunction "2_2") (pintype "passive"))
      (node (ref "C23") (pin "2") (pinfunction "2_2") (pintype "passive"))
      (node (ref "C24") (pin "2") (pinfunction "2_2") (pintype "passive"))
      (node (ref "C25") (pin "2") (pinfunction "2_2") (pintype "passive"))
      (node (ref "C26") (pin "2") (pinfunction "2_2") (pintype "passive"))
      (node (ref "C27") (pin "2") (pinfunction "2_2") (pintype "passive"))
      (node (ref "C28") (pin "2") (pinfunction "2_2") (pintype "passive"))
      (node (ref "C29") (pin "2") (pinfunction "2_2") (pintype "passive"))
      (node (ref "C3") (pin "P$2") (pinfunction "V-_P$2") (pintype "bidirectional"))
      (node (ref "C30") (pin "2") (pinfunction "2_2") (pintype "passive"))
      (node (ref "C31") (pin "2") (pinfunction "2_2") (pintype "passive"))
      (node (ref "C32") (pin "2") (pinfunction "2_2") (pintype "passive"))
      (node (ref "C33") (pin "2") (pinfunction "2_2") (pintype "passive"))
      (node (ref "C34") (pin "2") (pinfunction "2_2") (pintype "passive"))
      (node (ref "C35") (pin "2") (pinfunction "2_2") (pintype "passive"))
      (node (ref "C36") (pin "2") (pinfunction "2_2") (pintype "passive"))
      (node (ref "C37") (pin "2") (pinfunction "2_2") (pintype "passive"))
      (node (ref "C39") (pin "2") (pinfunction "2_2") (pintype "passive"))
      (node (ref "C4") (pin "2") (pinfunction "2_2") (pintype "passive"))
      (node (ref "C40") (pin "2") (pinfunction "2_2") (pintype "passive"))
      (node (ref "C41") (pin "2") (pinfunction "2_2") (pintype "passive"))
      (node (ref "C42") (pin "2") (pinfunction "2_2") (pintype "passive"))
      (node (ref "C43") (pin "2") (pinfunction "2_2") (pintype "passive"))
      (node (ref "C44") (pin "2") (pinfunction "2_2") (pintype "passive"))
      (node (ref "C45") (pin "2") (pinfunction "2_2") (pintype "passive"))
      (node (ref "C46") (pin "2") (pinfunction "2_2") (pintype "passive"))
      (node (ref "C47") (pin "2") (pinfunction "2_2") (pintype "passive"))
      (node (ref "C48") (pin "2") (pinfunction "2_2") (pintype "passive"))
      (node (ref "C49") (pin "2") (pinfunction "2_2") (pintype "passive"))
      (node (ref "C5") (pin "2") (pinfunction "2_2") (pintype "passive"))
      (node (ref "C50") (pin "2") (pinfunction "2_2") (pintype "passive"))
      (node (ref "C8") (pin "2") (pinfunction "2_2") (pintype "passive"))
      (node (ref "C9") (pin "2") (pinfunction "2_2") (pintype "passive"))
      (node (ref "D4") (pin "P$2") (pinfunction "OUT_P$2") (pintype "bidirectional"))
      (node (ref "J1") (pin "5") (pinfunction "5_5") (pintype "passive"))
      (node (ref "J2") (pin "15") (pinfunction "15_15") (pintype "passive"))
      (node (ref "J2") (pin "2") (pinfunction "2_2") (pintype "passive"))
      (node (ref "J3") (pin "11") (pinfunction "11_11") (pintype "passive"))
      (node (ref "J3") (pin "17") (pinfunction "17_17") (pintype "passive"))
      (node (ref "JP1") (pin "2") (pinfunction "2_2") (pintype "passive"))
      (node (ref "R12") (pin "1") (pinfunction "1_1") (pintype "passive"))
      (node (ref "R14") (pin "1") (pinfunction "1_1") (pintype "passive"))
      (node (ref "R18") (pin "1") (pinfunction "1_1") (pintype "passive"))
      (node (ref "R2") (pin "2") (pinfunction "2_2") (pintype "passive"))
      (node (ref "R22") (pin "2") (pinfunction "2_2") (pintype "passive"))
      (node (ref "R28") (pin "1") (pinfunction "1_1") (pintype "passive"))
      (node (ref "R30") (pin "1") (pinfunction "1_1") (pintype "passive"))
      (node (ref "R33") (pin "1") (pinfunction "1_1") (pintype "passive"))
      (node (ref "R36") (pin "1") (pinfunction "1_1") (pintype "passive"))
      (node (ref "R37") (pin "2") (pinfunction "2_2") (pintype "passive"))
      (node (ref "R38") (pin "2") (pinfunction "2_2") (pintype "passive"))
      (node (ref "R4") (pin "1") (pinfunction "1_1") (pintype "passive"))
      (node (ref "R7") (pin "1") (pinfunction "1_1") (pintype "passive"))
      (node (ref "R9") (pin "1") (pinfunction "1_1") (pintype "passive"))
      (node (ref "S1") (pin "P$1") (pinfunction "P$1_P$1") (pintype "bidirectional"))
      (node (ref "S2") (pin "P$1") (pinfunction "1H_P$1") (pintype "bidirectional"))
      (node (ref "S2") (pin "P$4") (pinfunction "1L_P$4") (pintype "bidirectional"))
      (node (ref "S3") (pin "P$1") (pinfunction "I_P$1") (pintype "bidirectional"))
      (node (ref "S4") (pin "P$1") (pinfunction "P$1_P$1") (pintype "bidirectional"))
      (node (ref "S5") (pin "P$1") (pinfunction "P$1_P$1") (pintype "bidirectional"))
      (node (ref "S6") (pin "P$1") (pinfunction "P$1_P$1") (pintype "bidirectional"))
      (node (ref "TR1") (pin "P$4") (pinfunction "S_P$4") (pintype "bidirectional"))
      (node (ref "TR2") (pin "P$4") (pinfunction "S_P$4") (pintype "bidirectional"))
      (node (ref "TR3") (pin "2") (pinfunction "S_2") (pintype "bidirectional"))
      (node (ref "U$1") (pin "3") (pinfunction "GND_3") (pintype "power_in"))
      (node (ref "U$1") (pin "6") (pinfunction "DAP_6") (pintype "power_in"))
      (node (ref "U1") (pin "1") (pinfunction "GND1_1") (pintype "power_in"))
      (node (ref "U1") (pin "15") (pinfunction "GND15_15") (pintype "power_in"))
      (node (ref "U1") (pin "38") (pinfunction "GND38_38") (pintype "power_in"))
      (node (ref "U1") (pin "39") (pinfunction "GND39_39") (pintype "bidirectional"))
      (node (ref "U1") (pin "40") (pinfunction "GND40_40") (pintype "bidirectional"))
      (node (ref "U1") (pin "41") (pinfunction "GND41_41") (pintype "bidirectional"))
      (node (ref "U1") (pin "42") (pinfunction "GND42_42") (pintype "bidirectional"))
      (node (ref "U1") (pin "43") (pinfunction "GND43_43") (pintype "power_in"))
      (node (ref "U1") (pin "44") (pinfunction "GND44_44") (pintype "bidirectional"))
      (node (ref "U1") (pin "45") (pinfunction "GND45_45") (pintype "bidirectional"))
      (node (ref "U1") (pin "46") (pinfunction "GND46_46") (pintype "bidirectional"))
      (node (ref "U1") (pin "47") (pinfunction "GND47_47") (pintype "bidirectional"))
      (node (ref "U10") (pin "2") (pinfunction "GND_2") (pintype "power_in"))
      (node (ref "U11") (pin "2") (pinfunction "GND_2") (pintype "power_in"))
      (node (ref "U2") (pin "P$13") (pinfunction "PGND1_P$13") (pintype "bidirectional"))
      (node (ref "U2") (pin "P$17") (pinfunction "PGND2_P$17") (pintype "bidirectional"))
      (node (ref "U2") (pin "P$4") (pinfunction "GND_P$4") (pintype "bidirectional"))
      (node (ref "U2") (pin "P$5") (pinfunction "VS3_P$5") (pintype "bidirectional"))
      (node (ref "U2") (pin "P$7") (pinfunction "VS1_P$7") (pintype "bidirectional"))
      (node (ref "U2") (pin "P$8") (pinfunction "PWM_P$8") (pintype "bidirectional"))
      (node (ref "U3") (pin "P$4") (pinfunction "GND_P$4") (pintype "bidirectional"))
      (node (ref "U3") (pin "P$9") (pinfunction "PWPD_P$9") (pintype "bidirectional"))
      (node (ref "U4") (pin "1") (pinfunction "~{ON}_1") (pintype "passive"))
      (node (ref "U4") (pin "3") (pinfunction "GND_3") (pintype "power_in"))
      (node (ref "U5") (pin "1") (pinfunction "VSS_1") (pintype "passive"))
      (node (ref "U6") (pin "2") (pinfunction "GND_2") (pintype "power_in"))
      (node (ref "U7") (pin "7") (pinfunction "GND_7") (pintype "passive"))
      (node (ref "U8") (pin "14") (pinfunction "GND_14") (pintype "passive"))
      (node (ref "U9") (pin "4") (pinfunction "VSS_4") (pintype "power_in"))
      (node (ref "X8") (pin "1") (pinfunction "P$1_1") (pintype "bidirectional"))
    )
    (net (code "54") (name "Net-(A1-IN+)") (class "Default")
      (node (ref "A1") (pin "P$3") (pinfunction "IN+_P$3") (pintype "bidirectional"))
      (node (ref "R5") (pin "P$1") (pinfunction "V1_P$1") (pintype "bidirectional"))
    )
    (net (code "55") (name "Net-(A1-IN-)") (class "Default")
      (node (ref "A1") (pin "P$4") (pinfunction "IN-_P$4") (pintype "bidirectional"))
      (node (ref "R5") (pin "P$2") (pinfunction "V2_P$2") (pintype "bidirectional"))
    )
    (net (code "56") (name "Net-(A2-IN+)") (class "Default")
      (node (ref "A2") (pin "P$3") (pinfunction "IN+_P$3") (pintype "bidirectional"))
      (node (ref "R26") (pin "P$1") (pinfunction "V1_P$1") (pintype "bidirectional"))
    )
    (net (code "57") (name "Net-(A2-IN-)") (class "Default")
      (node (ref "A2") (pin "P$4") (pinfunction "IN-_P$4") (pintype "bidirectional"))
      (node (ref "R26") (pin "P$2") (pinfunction "V2_P$2") (pintype "bidirectional"))
    )
    (net (code "58") (name "Net-(A2-VS)") (class "Default")
      (node (ref "A2") (pin "P$6") (pinfunction "VS_P$6") (pintype "bidirectional"))
      (node (ref "C27") (pin "1") (pinfunction "1_1") (pintype "passive"))
      (node (ref "R25") (pin "2") (pinfunction "2_2") (pintype "passive"))
      (node (ref "R26") (pin "P$3") (pinfunction "I1_P$3") (pintype "bidirectional"))
      (node (ref "R29") (pin "2") (pinfunction "2_2") (pintype "passive"))
      (node (ref "X9") (pin "1") (pinfunction "P$1_1") (pintype "bidirectional"))
    )
    (net (code "59") (name "Net-(A3-IN+)") (class "Default")
      (node (ref "A3") (pin "P$3") (pinfunction "IN+_P$3") (pintype "bidirectional"))
      (node (ref "R31") (pin "P$1") (pinfunction "V1_P$1") (pintype "bidirectional"))
    )
    (net (code "60") (name "Net-(A3-IN-)") (class "Default")
      (node (ref "A3") (pin "P$4") (pinfunction "IN-_P$4") (pintype "bidirectional"))
      (node (ref "R31") (pin "P$2") (pinfunction "V2_P$2") (pintype "bidirectional"))
    )
    (net (code "61") (name "Net-(A4-IN+)") (class "Default")
      (node (ref "A4") (pin "P$3") (pinfunction "IN+_P$3") (pintype "bidirectional"))
      (node (ref "R34") (pin "3") (pinfunction "V1_3") (pintype "bidirectional"))
    )
    (net (code "62") (name "Net-(A4-IN-)") (class "Default")
      (node (ref "A4") (pin "P$4") (pinfunction "IN-_P$4") (pintype "bidirectional"))
      (node (ref "R34") (pin "4") (pinfunction "V2_4") (pintype "bidirectional"))
    )
    (net (code "63") (name "Net-(A4-OUT)") (class "Default")
      (node (ref "A4") (pin "P$1") (pinfunction "OUT_P$1") (pintype "bidirectional"))
      (node (ref "R35") (pin "2") (pinfunction "2_2") (pintype "passive"))
    )
    (net (code "64") (name "Net-(A4-VS)") (class "Default")
      (node (ref "A4") (pin "P$6") (pinfunction "VS_P$6") (pintype "bidirectional"))
      (node (ref "C18") (pin "1") (pinfunction "1_1") (pintype "passive"))
      (node (ref "C37") (pin "1") (pinfunction "1_1") (pintype "passive"))
      (node (ref "R19") (pin "2") (pinfunction "2_2") (pintype "passive"))
      (node (ref "R34") (pin "1") (pinfunction "I1_1") (pintype "bidirectional"))
      (node (ref "U4") (pin "6") (pinfunction "OUT_2_6") (pintype "output"))
      (node (ref "U4") (pin "8") (pinfunction "OUT_8") (pintype "output"))
    )
    (net (code "65") (name "Net-(C3-V+)") (class "Default")
      (node (ref "C2") (pin "1") (pinfunction "1_1") (pintype "passive"))
      (node (ref "C3") (pin "P$1") (pinfunction "V+_P$1") (pintype "bidirectional"))
      (node (ref "C4") (pin "1") (pinfunction "1_1") (pintype "passive"))
      (node (ref "R5") (pin "P$4") (pinfunction "I2_P$4") (pintype "bidirectional"))
      (node (ref "R6") (pin "2") (pinfunction "2_2") (pintype "passive"))
      (node (ref "R8") (pin "2") (pinfunction "2_2") (pintype "passive"))
      (node (ref "U2") (pin "P$1") (pinfunction "VCC_P$1") (pintype "bidirectional"))
      (node (ref "U2") (pin "P$16") (pinfunction "VIN_P$16") (pintype "bidirectional"))
      (node (ref "U2") (pin "P$6") (pinfunction "VS2_P$6") (pintype "bidirectional"))
    )
    (net (code "66") (name "Net-(C13-Pad1)") (class "Default")
      (node (ref "C13") (pin "1") (pinfunction "1_1") (pintype "passive"))
      (node (ref "R15") (pin "1") (pinfunction "1_1") (pintype "passive"))
    )
    (net (code "67") (name "Net-(C29-Pad1)") (class "Default")
      (node (ref "C29") (pin "1") (pinfunction "1_1") (pintype "passive"))
      (node (ref "J3") (pin "20") (pinfunction "20_20") (pintype "passive"))
    )
    (net (code "68") (name "Net-(C30-Pad1)") (class "Default")
      (node (ref "C30") (pin "1") (pinfunction "1_1") (pintype "passive"))
      (node (ref "J3") (pin "5") (pinfunction "5_5") (pintype "passive"))
    )
    (net (code "69") (name "Net-(C31-Pad1)") (class "Default")
      (node (ref "C31") (pin "1") (pinfunction "1_1") (pintype "passive"))
      (node (ref "J3") (pin "24") (pinfunction "24_24") (pintype "passive"))
    )
    (net (code "70") (name "Net-(C32-Pad1)") (class "Default")
      (node (ref "C32") (pin "1") (pinfunction "1_1") (pintype "passive"))
      (node (ref "J3") (pin "22") (pinfunction "22_22") (pintype "passive"))
    )
    (net (code "71") (name "Net-(C33-Pad1)") (class "Default")
      (node (ref "C33") (pin "1") (pinfunction "1_1") (pintype "passive"))
      (node (ref "J3") (pin "18") (pinfunction "18_18") (pintype "passive"))
    )
    (net (code "72") (name "Net-(C42-Pad1)") (class "Default")
      (node (ref "C42") (pin "1") (pinfunction "1_1") (pintype "passive"))
      (node (ref "J2") (pin "6") (pinfunction "6_6") (pintype "passive"))
      (node (ref "R39") (pin "2") (pinfunction "2_2") (pintype "passive"))
    )
    (net (code "73") (name "Net-(D1-IN)") (class "Default")
      (node (ref "D1") (pin "P$1") (pinfunction "IN_P$1") (pintype "bidirectional"))
      (node (ref "R23") (pin "2") (pinfunction "2_2") (pintype "passive"))
      (node (ref "X5") (pin "1") (pinfunction "P$1_1") (pintype "bidirectional"))
    )
    (net (code "74") (name "Net-(D2-IN)") (class "Default")
      (node (ref "C38") (pin "1") (pinfunction "1_1") (pintype "passive"))
      (node (ref "D2") (pin "P$1") (pinfunction "IN_P$1") (pintype "bidirectional"))
      (node (ref "D4") (pin "P$1") (pinfunction "IN_P$1") (pintype "bidirectional"))
      (node (ref "L3") (pin "P$1") (pinfunction "P$1_P$1") (pintype "bidirectional"))
      (node (ref "TR4") (pin "3") (pinfunction "D_3") (pintype "bidirectional"))
    )
    (net (code "75") (name "Net-(D2-OUT)") (class "Default")
      (node (ref "C40") (pin "1") (pinfunction "1_1") (pintype "passive"))
      (node (ref "D2") (pin "P$2") (pinfunction "OUT_P$2") (pintype "bidirectional"))
      (node (ref "J3") (pin "21") (pinfunction "21_21") (pintype "passive"))
    )
    (net (code "76") (name "Net-(D3-IN)") (class "Default")
      (node (ref "C39") (pin "1") (pinfunction "1_1") (pintype "passive"))
      (node (ref "D3") (pin "P$1") (pinfunction "IN_P$1") (pintype "bidirectional"))
      (node (ref "J3") (pin "23") (pinfunction "23_23") (pintype "passive"))
    )
    (net (code "77") (name "Net-(D3-OUT)") (class "Default")
      (node (ref "C38") (pin "2") (pinfunction "2_2") (pintype "passive"))
      (node (ref "D3") (pin "P$2") (pinfunction "OUT_P$2") (pintype "bidirectional"))
    )
    (net (code "78") (name "Net-(J2-Pad8)") (class "Default")
      (node (ref "J2") (pin "8") (pinfunction "8_8") (pintype "passive"))
      (node (ref "R38") (pin "1") (pinfunction "1_1") (pintype "passive"))
    )
    (net (code "79") (name "Net-(LED1-PadA)") (class "Default")
      (node (ref "LED1") (pin "A") (pinfunction "A_A") (pintype "passive"))
      (node (ref "R19") (pin "1") (pinfunction "1_1") (pintype "passive"))
    )
    (net (code "80") (name "Net-(R10-PadP$2)") (class "Default")
      (node (ref "R10") (pin "P$2") (pinfunction "P$2_P$2") (pintype "bidirectional"))
      (node (ref "R8") (pin "1") (pinfunction "1_1") (pintype "passive"))
    )
    (net (code "81") (name "Net-(R14-Pad2)") (class "Default")
      (node (ref "R14") (pin "2") (pinfunction "2_2") (pintype "passive"))
      (node (ref "R16") (pin "P$2") (pinfunction "P$2_P$2") (pintype "bidirectional"))
    )
    (net (code "82") (name "Net-(R20-PadP$2)") (class "Default")
      (node (ref "R20") (pin "P$2") (pinfunction "P$2_P$2") (pintype "bidirectional"))
      (node (ref "R21") (pin "2") (pinfunction "2_2") (pintype "passive"))
    )
    (net (code "83") (name "Net-(R34-I2)") (class "Default")
      (node (ref "R24") (pin "1") (pinfunction "1_1") (pintype "passive"))
      (node (ref "R34") (pin "2") (pinfunction "I2_2") (pintype "bidirectional"))
    )
    (net (code "84") (name "Net-(TR1-D-PadP$1)") (class "Default")
      (node (ref "TR1") (pin "P$1") (pinfunction "D_P$1") (pintype "bidirectional"))
      (node (ref "TR1") (pin "P$2") (pinfunction "D_P$2") (pintype "bidirectional"))
      (node (ref "TR1") (pin "P$5") (pinfunction "D_P$5") (pintype "bidirectional"))
      (node (ref "TR1") (pin "P$6") (pinfunction "D_P$6") (pintype "bidirectional"))
      (node (ref "X1") (pin "GND") (pinfunction "GND_GND") (pintype "bidirectional"))
    )
    (net (code "85") (name "Net-(TR2-D-PadP$1)") (class "Default")
      (node (ref "TR2") (pin "P$1") (pinfunction "D_P$1") (pintype "bidirectional"))
      (node (ref "TR2") (pin "P$2") (pinfunction "D_P$2") (pintype "bidirectional"))
      (node (ref "TR2") (pin "P$5") (pinfunction "D_P$5") (pintype "bidirectional"))
      (node (ref "TR2") (pin "P$6") (pinfunction "D_P$6") (pintype "bidirectional"))
      (node (ref "X2") (pin "GND") (pinfunction "GND_GND") (pintype "bidirectional"))
    )
    (net (code "86") (name "Net-(TR3-D)") (class "Default")
      (node (ref "LED1") (pin "C") (pinfunction "C_C") (pintype "passive"))
      (node (ref "TR3") (pin "3") (pinfunction "D_3") (pintype "bidirectional"))
    )
    (net (code "87") (name "Net-(TR3-G)") (class "Default")
      (node (ref "R35") (pin "1") (pinfunction "1_1") (pintype "passive"))
      (node (ref "R36") (pin "2") (pinfunction "2_2") (pintype "passive"))
      (node (ref "TR3") (pin "1") (pinfunction "G_1") (pintype "bidirectional"))
    )
    (net (code "88") (name "Net-(TR4-G)") (class "Default")
      (node (ref "J3") (pin "2") (pinfunction "2_2") (pintype "passive"))
      (node (ref "TR4") (pin "1") (pinfunction "G_1") (pintype "bidirectional"))
    )
    (net (code "89") (name "Net-(TR4-S)") (class "Default")
      (node (ref "J3") (pin "3") (pinfunction "3_3") (pintype "passive"))
      (node (ref "R37") (pin "1") (pinfunction "1_1") (pintype "passive"))
      (node (ref "TR4") (pin "2") (pinfunction "S_2") (pintype "bidirectional"))
    )
    (net (code "90") (name "Net-(U$1-ADJ)") (class "Default")
      (node (ref "R20") (pin "P$1") (pinfunction "P$1_P$1") (pintype "bidirectional"))
      (node (ref "R20") (pin "P$3") (pinfunction "P$3_P$3") (pintype "bidirectional"))
      (node (ref "R22") (pin "1") (pinfunction "1_1") (pintype "passive"))
      (node (ref "U$1") (pin "5") (pinfunction "ADJ_5") (pintype "input"))
    )
    (net (code "91") (name "Net-(U$1-OUT)") (class "Default")
      (node (ref "C20") (pin "1") (pinfunction "1_1") (pintype "passive"))
      (node (ref "R21") (pin "1") (pinfunction "1_1") (pintype "passive"))
      (node (ref "R25") (pin "1") (pinfunction "1_1") (pintype "passive"))
      (node (ref "U$1") (pin "4") (pinfunction "OUT_4") (pintype "power_in"))
    )
    (net (code "92") (name "Net-(U2-BST1)") (class "Default")
      (node (ref "C6") (pin "2") (pinfunction "2_2") (pintype "passive"))
      (node (ref "U2") (pin "P$15") (pinfunction "BST1_P$15") (pintype "bidirectional"))
    )
    (net (code "93") (name "Net-(U2-BST2)") (class "Default")
      (node (ref "C7") (pin "2") (pinfunction "2_2") (pintype "passive"))
      (node (ref "U2") (pin "P$11") (pinfunction "BST2_P$11") (pintype "bidirectional"))
    )
    (net (code "94") (name "Net-(U2-MPPC)") (class "Default")
      (node (ref "R10") (pin "P$1") (pinfunction "P$1_P$1") (pintype "bidirectional"))
      (node (ref "R10") (pin "P$3") (pinfunction "P$3_P$3") (pintype "bidirectional"))
      (node (ref "R9") (pin "2") (pinfunction "2_2") (pintype "passive"))
      (node (ref "U2") (pin "P$3") (pinfunction "MPPC_P$3") (pintype "bidirectional"))
    )
    (net (code "95") (name "Net-(U2-RUN)") (class "Default")
      (node (ref "R6") (pin "1") (pinfunction "1_1") (pintype "passive"))
      (node (ref "R7") (pin "2") (pinfunction "2_2") (pintype "passive"))
      (node (ref "U2") (pin "P$2") (pinfunction "RUN_P$2") (pintype "bidirectional"))
    )
    (net (code "96") (name "Net-(U2-SW1)") (class "Default")
      (node (ref "C6") (pin "1") (pinfunction "1_1") (pintype "passive"))
      (node (ref "L1") (pin "P$1") (pinfunction "P$1_P$1") (pintype "bidirectional"))
      (node (ref "U2") (pin "P$14") (pinfunction "SW1_P$14") (pintype "bidirectional"))
    )
    (net (code "97") (name "Net-(U2-SW2)") (class "Default")
      (node (ref "C7") (pin "1") (pinfunction "1_1") (pintype "passive"))
      (node (ref "L1") (pin "P$2") (pinfunction "P$2_P$2") (pintype "bidirectional"))
      (node (ref "U2") (pin "P$12") (pinfunction "SW2_P$12") (pintype "bidirectional"))
    )
    (net (code "98") (name "Net-(U2-VOUT)") (class "Default")
      (node (ref "C5") (pin "1") (pinfunction "1_1") (pintype "passive"))
      (node (ref "R23") (pin "1") (pinfunction "1_1") (pintype "passive"))
      (node (ref "U2") (pin "P$10") (pinfunction "VOUT_P$10") (pintype "bidirectional"))
    )
    (net (code "99") (name "Net-(U3-BOOT)") (class "Default")
      (node (ref "C11") (pin "1") (pinfunction "1_1") (pintype "passive"))
      (node (ref "U3") (pin "P$1") (pinfunction "BOOT_P$1") (pintype "bidirectional"))
    )
    (net (code "100") (name "Net-(U3-COMP)") (class "Default")
      (node (ref "C14") (pin "1") (pinfunction "1_1") (pintype "passive"))
      (node (ref "R15") (pin "2") (pinfunction "2_2") (pintype "passive"))
      (node (ref "U3") (pin "P$7") (pinfunction "COMP_P$7") (pintype "bidirectional"))
    )
    (net (code "101") (name "Net-(U3-EN)") (class "Default")
      (node (ref "R12") (pin "2") (pinfunction "2_2") (pintype "passive"))
      (node (ref "R13") (pin "1") (pinfunction "1_1") (pintype "passive"))
      (node (ref "U3") (pin "P$6") (pinfunction "EN_P$6") (pintype "bidirectional"))
    )
    (net (code "102") (name "Net-(U3-PH)") (class "Default")
      (node (ref "C11") (pin "2") (pinfunction "2_2") (pintype "passive"))
      (node (ref "L2") (pin "P$1") (pinfunction "P$1_P$1") (pintype "bidirectional"))
      (node (ref "U3") (pin "P$3") (pinfunction "PH_P$3") (pintype "bidirectional"))
    )
    (net (code "103") (name "Net-(U3-SS)") (class "Default")
      (node (ref "C10") (pin "1") (pinfunction "1_1") (pintype "passive"))
      (node (ref "U3") (pin "P$5") (pinfunction "SS_P$5") (pintype "bidirectional"))
    )
    (net (code "104") (name "Net-(U3-VIN)") (class "Default")
      (node (ref "C8") (pin "1") (pinfunction "1_1") (pintype "passive"))
      (node (ref "C9") (pin "1") (pinfunction "1_1") (pintype "passive"))
      (node (ref "J1") (pin "1") (pinfunction "1_1") (pintype "passive"))
      (node (ref "R13") (pin "2") (pinfunction "2_2") (pintype "passive"))
      (node (ref "U3") (pin "P$2") (pinfunction "VIN_P$2") (pintype "bidirectional"))
    )
    (net (code "105") (name "Net-(U3-VSENS)") (class "Default")
      (node (ref "C12") (pin "2") (pinfunction "2_2") (pintype "passive"))
      (node (ref "R11") (pin "1") (pinfunction "1_1") (pintype "passive"))
      (node (ref "R16") (pin "P$1") (pinfunction "P$1_P$1") (pintype "bidirectional"))
      (node (ref "R16") (pin "P$3") (pinfunction "P$3_P$3") (pintype "bidirectional"))
      (node (ref "U3") (pin "P$8") (pinfunction "VSENS_P$8") (pintype "bidirectional"))
    )
    (net (code "106") (name "Net-(U4-IN)") (class "Default")
      (node (ref "C12") (pin "1") (pinfunction "1_1") (pintype "passive"))
      (node (ref "C15") (pin "1") (pinfunction "1_1") (pintype "passive"))
      (node (ref "C16") (pin "1") (pinfunction "1_1") (pintype "passive"))
      (node (ref "C17") (pin "1") (pinfunction "1_1") (pintype "passive"))
      (node (ref "L2") (pin "P$2") (pinfunction "P$2_P$2") (pintype "bidirectional"))
      (node (ref "R11") (pin "2") (pinfunction "2_2") (pintype "passive"))
      (node (ref "R17") (pin "2") (pinfunction "2_2") (pintype "passive"))
      (node (ref "U4") (pin "5") (pinfunction "IN_2_5") (pintype "input"))
      (node (ref "U4") (pin "7") (pinfunction "IN_7") (pintype "input"))
    )
    (net (code "107") (name "Net-(U4-ISET)") (class "Default")
      (node (ref "R18") (pin "2") (pinfunction "2_2") (pintype "passive"))
      (node (ref "U4") (pin "4") (pinfunction "ISET_4") (pintype "passive"))
    )
    (net (code "108") (name "Net-(U4-~{FAULT})") (class "Default")
      (node (ref "R17") (pin "1") (pinfunction "1_1") (pintype "passive"))
      (node (ref "U4") (pin "2") (pinfunction "~{FAULT}_2") (pintype "passive"))
    )
    (net (code "109") (name "Net-(U6-VIN)") (class "Default")
      (node (ref "U6") (pin "3") (pinfunction "VIN_3") (pintype "input"))
      (node (ref "U8") (pin "8") (pinfunction "D_8") (pintype "passive"))
    )
    (net (code "110") (name "Net-(U10-OUT)") (class "Default")
      (node (ref "C45") (pin "1") (pinfunction "1_1") (pintype "passive"))
      (node (ref "J2") (pin "10") (pinfunction "10_10") (pintype "passive"))
      (node (ref "U10") (pin "5") (pinfunction "OUT_5") (pintype "power_in"))
    )
    (net (code "111") (name "Net-(U11-OUT)") (class "Default")
      (node (ref "C46") (pin "1") (pinfunction "1_1") (pintype "passive"))
      (node (ref "J2") (pin "4") (pinfunction "4_4") (pintype "passive"))
      (node (ref "U11") (pin "5") (pinfunction "OUT_5") (pintype "passive"))
    )
    (net (code "112") (name "VCC") (class "Default")
      (node (ref "C21") (pin "1") (pinfunction "1_1") (pintype "passive"))
      (node (ref "C22") (pin "1") (pinfunction "1_1") (pintype "passive"))
      (node (ref "C23") (pin "1") (pinfunction "1_1") (pintype "passive"))
      (node (ref "C24") (pin "1") (pinfunction "1_1") (pintype "passive"))
      (node (ref "C25") (pin "1") (pinfunction "1_1") (pintype "passive"))
      (node (ref "C34") (pin "1") (pinfunction "1_1") (pintype "passive"))
      (node (ref "C36") (pin "1") (pinfunction "1_1") (pintype "passive"))
      (node (ref "C41") (pin "1") (pinfunction "1_1") (pintype "passive"))
      (node (ref "C43") (pin "1") (pinfunction "1_1") (pintype "passive"))
      (node (ref "C44") (pin "1") (pinfunction "1_1") (pintype "passive"))
      (node (ref "J2") (pin "11") (pinfunction "11_11") (pintype "passive"))
      (node (ref "J3") (pin "15") (pinfunction "15_15") (pintype "passive"))
      (node (ref "J3") (pin "16") (pinfunction "16_16") (pintype "passive"))
      (node (ref "J3") (pin "8") (pinfunction "8_8") (pintype "passive"))
      (node (ref "JP1") (pin "1") (pinfunction "1_1") (pintype "passive"))
      (node (ref "L3") (pin "P$2") (pinfunction "P$2_P$2") (pintype "bidirectional"))
      (node (ref "R1") (pin "2") (pinfunction "2_2") (pintype "passive"))
      (node (ref "R26") (pin "P$4") (pinfunction "I2_P$4") (pintype "bidirectional"))
      (node (ref "R3") (pin "2") (pinfunction "2_2") (pintype "passive"))
      (node (ref "R39") (pin "1") (pinfunction "1_1") (pintype "passive"))
      (node (ref "R40") (pin "1") (pinfunction "1_1") (pintype "passive"))
      (node (ref "R41") (pin "1") (pinfunction "1_1") (pintype "passive"))
      (node (ref "R42") (pin "2") (pinfunction "2_2") (pintype "passive"))
      (node (ref "R43") (pin "2") (pinfunction "2_2") (pintype "passive"))
      (node (ref "R44") (pin "2") (pinfunction "2_2") (pintype "passive"))
      (node (ref "S2") (pin "P$3") (pinfunction "2H_P$3") (pintype "bidirectional"))
      (node (ref "S2") (pin "P$6") (pinfunction "2L_P$6") (pintype "bidirectional"))
      (node (ref "U1") (pin "2") (pinfunction "3V3_2") (pintype "power_in"))
      (node (ref "U10") (pin "1") (pinfunction "IN_1") (pintype "power_in"))
      (node (ref "U10") (pin "3") (pinfunction "EN_3") (pintype "input"))
      (node (ref "U11") (pin "1") (pinfunction "IN_1") (pintype "power_in"))
      (node (ref "U11") (pin "3") (pinfunction "EN_3") (pintype "input"))
      (node (ref "U5") (pin "11") (pinfunction "VDD_11") (pintype "passive"))
      (node (ref "U6") (pin "1") (pinfunction "VDD_1") (pintype "power_in"))
      (node (ref "U7") (pin "14") (pinfunction "VCC_14") (pintype "power_in"))
      (node (ref "U8") (pin "13") (pinfunction "VDD_13") (pintype "power_in"))
      (node (ref "U8") (pin "2") (pinfunction "EN_2") (pintype "passive"))
      (node (ref "U9") (pin "7") (pinfunction "~{HOLD}_7") (pintype "input"))
      (node (ref "U9") (pin "8") (pinfunction "VDD_8") (pintype "power_in"))
    )
    (net (code "113") (name "unconnected-(J1-Pad2)") (class "Default")
      (node (ref "J1") (pin "2") (pinfunction "2_2") (pintype "passive"))
    )
    (net (code "114") (name "unconnected-(J1-Pad3)") (class "Default")
      (node (ref "J1") (pin "3") (pinfunction "3_3") (pintype "passive"))
    )
    (net (code "115") (name "unconnected-(J1-Pad4)") (class "Default")
      (node (ref "J1") (pin "4") (pinfunction "4_4") (pintype "passive"))
    )
    (net (code "116") (name "unconnected-(J2-Pad1)") (class "Default")
      (node (ref "J2") (pin "1") (pinfunction "1_1") (pintype "passive"))
    )
    (net (code "117") (name "unconnected-(J2-Pad23)") (class "Default")
      (node (ref "J2") (pin "23") (pinfunction "23_23") (pintype "passive"))
    )
    (net (code "118") (name "unconnected-(J2-Pad24)") (class "Default")
      (node (ref "J2") (pin "24") (pinfunction "24_24") (pintype "passive"))
    )
    (net (code "119") (name "unconnected-(J3-Pad1)") (class "Default")
      (node (ref "J3") (pin "1") (pinfunction "1_1") (pintype "passive"))
    )
    (net (code "120") (name "unconnected-(J3-Pad4)") (class "Default")
      (node (ref "J3") (pin "4") (pinfunction "4_4") (pintype "passive"))
    )
    (net (code "121") (name "unconnected-(J3-Pad6)") (class "Default")
      (node (ref "J3") (pin "6") (pinfunction "6_6") (pintype "passive"))
    )
    (net (code "122") (name "unconnected-(J3-Pad7)") (class "Default")
      (node (ref "J3") (pin "7") (pinfunction "7_7") (pintype "passive"))
    )
    (net (code "123") (name "unconnected-(J3-Pad19)") (class "Default")
      (node (ref "J3") (pin "19") (pinfunction "19_19") (pintype "passive"))
    )
    (net (code "124") (name "unconnected-(U$1-NC-Pad1)") (class "Default")
      (node (ref "U$1") (pin "1") (pinfunction "NC_1") (pintype "passive"))
    )
    (net (code "125") (name "unconnected-(U1-NC17-Pad17)") (class "Default")
      (node (ref "U1") (pin "17") (pinfunction "NC17_17") (pintype "no_connect"))
    )
    (net (code "126") (name "unconnected-(U1-NC18-Pad18)") (class "Default")
      (node (ref "U1") (pin "18") (pinfunction "NC18_18") (pintype "no_connect"))
    )
    (net (code "127") (name "unconnected-(U1-NC19-Pad19)") (class "Default")
      (node (ref "U1") (pin "19") (pinfunction "NC19_19") (pintype "no_connect"))
    )
    (net (code "128") (name "unconnected-(U1-NC20-Pad20)") (class "Default")
      (node (ref "U1") (pin "20") (pinfunction "NC20_20") (pintype "no_connect"))
    )
    (net (code "129") (name "unconnected-(U1-NC21-Pad21)") (class "Default")
      (node (ref "U1") (pin "21") (pinfunction "NC21_21") (pintype "no_connect"))
    )
    (net (code "130") (name "unconnected-(U1-NC22-Pad22)") (class "Default")
      (node (ref "U1") (pin "22") (pinfunction "NC22_22") (pintype "no_connect"))
    )
    (net (code "131") (name "unconnected-(U1-NC27-Pad27)") (class "Default")
      (node (ref "U1") (pin "27") (pinfunction "NC27_27") (pintype "no_connect"))
    )
    (net (code "132") (name "unconnected-(U1-NC28-Pad28)") (class "Default")
      (node (ref "U1") (pin "28") (pinfunction "NC28_28") (pintype "no_connect"))
    )
    (net (code "133") (name "unconnected-(U1-NC32-Pad32)") (class "Default")
      (node (ref "U1") (pin "32") (pinfunction "NC32_32") (pintype "no_connect"))
    )
    (net (code "134") (name "unconnected-(U2-PGOOD-PadP$9)") (class "Default")
      (node (ref "U2") (pin "P$9") (pinfunction "PGOOD_P$9") (pintype "bidirectional"))
    )
    (net (code "135") (name "unconnected-(U5-GPA4-Pad24)") (class "Default")
      (node (ref "U5") (pin "24") (pinfunction "GPA4_24") (pintype "passive"))
    )
    (net (code "136") (name "unconnected-(U5-GPA5-Pad25)") (class "Default")
      (node (ref "U5") (pin "25") (pinfunction "GPA5_25") (pintype "passive"))
    )
    (net (code "137") (name "unconnected-(U5-GPA6-Pad26)") (class "Default")
      (node (ref "U5") (pin "26") (pinfunction "GPA6_26") (pintype "passive"))
    )
    (net (code "138") (name "unconnected-(U5-GPA7-Pad27)") (class "Default")
      (node (ref "U5") (pin "27") (pinfunction "GPA7_27") (pintype "passive"))
    )
    (net (code "139") (name "unconnected-(U5-INTB-Pad18)") (class "Default")
      (node (ref "U5") (pin "18") (pinfunction "INTB_18") (pintype "passive"))
    )
    (net (code "140") (name "unconnected-(U5-NC-Pad28)") (class "Default")
      (node (ref "U5") (pin "28") (pinfunction "NC_28") (pintype "passive"))
    )
    (net (code "141") (name "unconnected-(U5-NC_2-Pad2)") (class "Default")
      (node (ref "U5") (pin "2") (pinfunction "NC_2_2") (pintype "passive"))
    )
    (net (code "142") (name "unconnected-(U5-NC_3-Pad17)") (class "Default")
      (node (ref "U5") (pin "17") (pinfunction "NC_3_17") (pintype "passive"))
    )
    (net (code "143") (name "unconnected-(U7-4A-Pad12)") (class "Default")
      (node (ref "U7") (pin "12") (pinfunction "4A_12") (pintype "bidirectional"))
    )
    (net (code "144") (name "unconnected-(U7-4B-Pad13)") (class "Default")
      (node (ref "U7") (pin "13") (pinfunction "4B_13") (pintype "bidirectional"))
    )
    (net (code "145") (name "unconnected-(U7-4Y-Pad11)") (class "Default")
      (node (ref "U7") (pin "11") (pinfunction "4Y_11") (pintype "bidirectional"))
    )
    (net (code "146") (name "unconnected-(U8-N.C.-Pad3)") (class "Default")
      (node (ref "U8") (pin "3") (pinfunction "N.C._3") (pintype "no_connect"))
    )
    (net (code "147") (name "unconnected-(U8-S7-Pad10)") (class "Default")
      (node (ref "U8") (pin "10") (pinfunction "S7_10") (pintype "bidirectional"))
    )
    (net (code "148") (name "unconnected-(U8-S8-Pad9)") (class "Default")
      (node (ref "U8") (pin "9") (pinfunction "S8_9") (pintype "bidirectional"))
    )
    (net (code "149") (name "unconnected-(U10-NC-Pad4)") (class "Default")
      (node (ref "U10") (pin "4") (pinfunction "NC_4") (pintype "passive"))
    )
    (net (code "150") (name "unconnected-(U11-NC-Pad4)") (class "Default")
      (node (ref "U11") (pin "4") (pinfunction "NC_4") (pintype "passive"))
    )
    (net (code "151") (name "unconnected-(X3-PadP$6)") (class "Default")
      (node (ref "X3") (pin "P$6") (pinfunction "P$6_P$6") (pintype "bidirectional"))
    )
  )
)
